# 03_-_28PINS_SCHEMATIC.net
KiCad netlist of a schematic drawn in Altium Designer
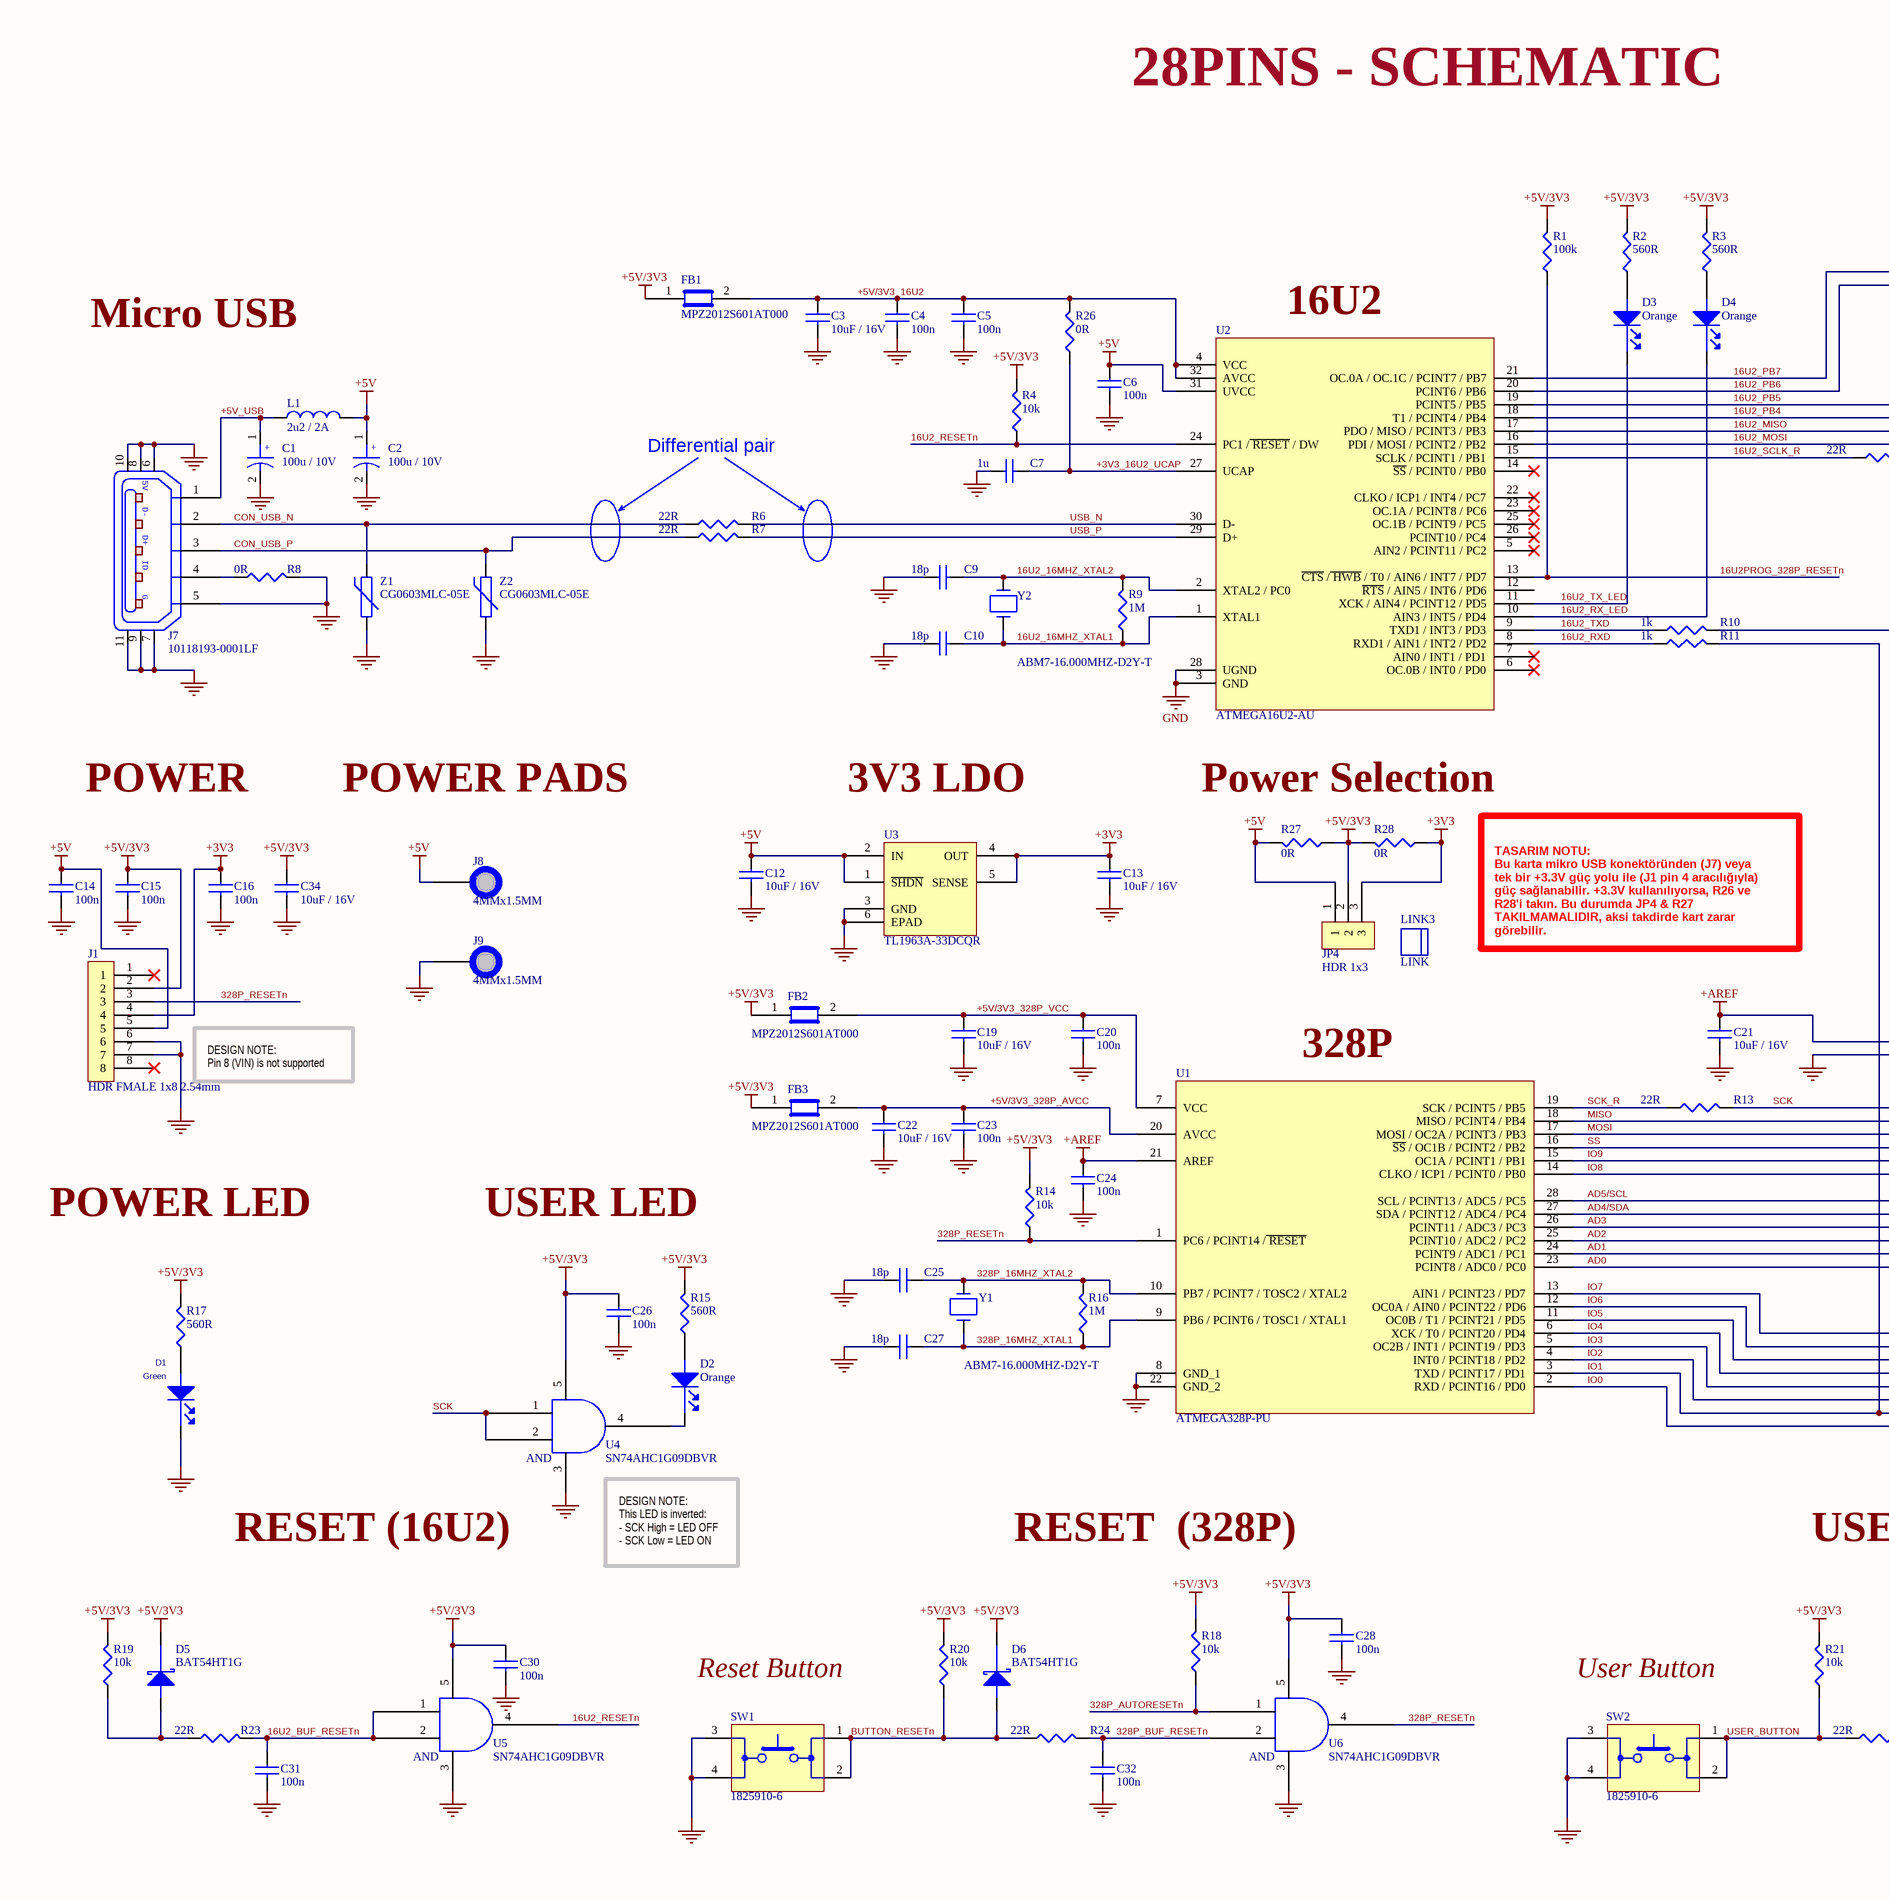
[diagram p0: [03] - 28PINS SCHEMATIC.SchDoc, left]
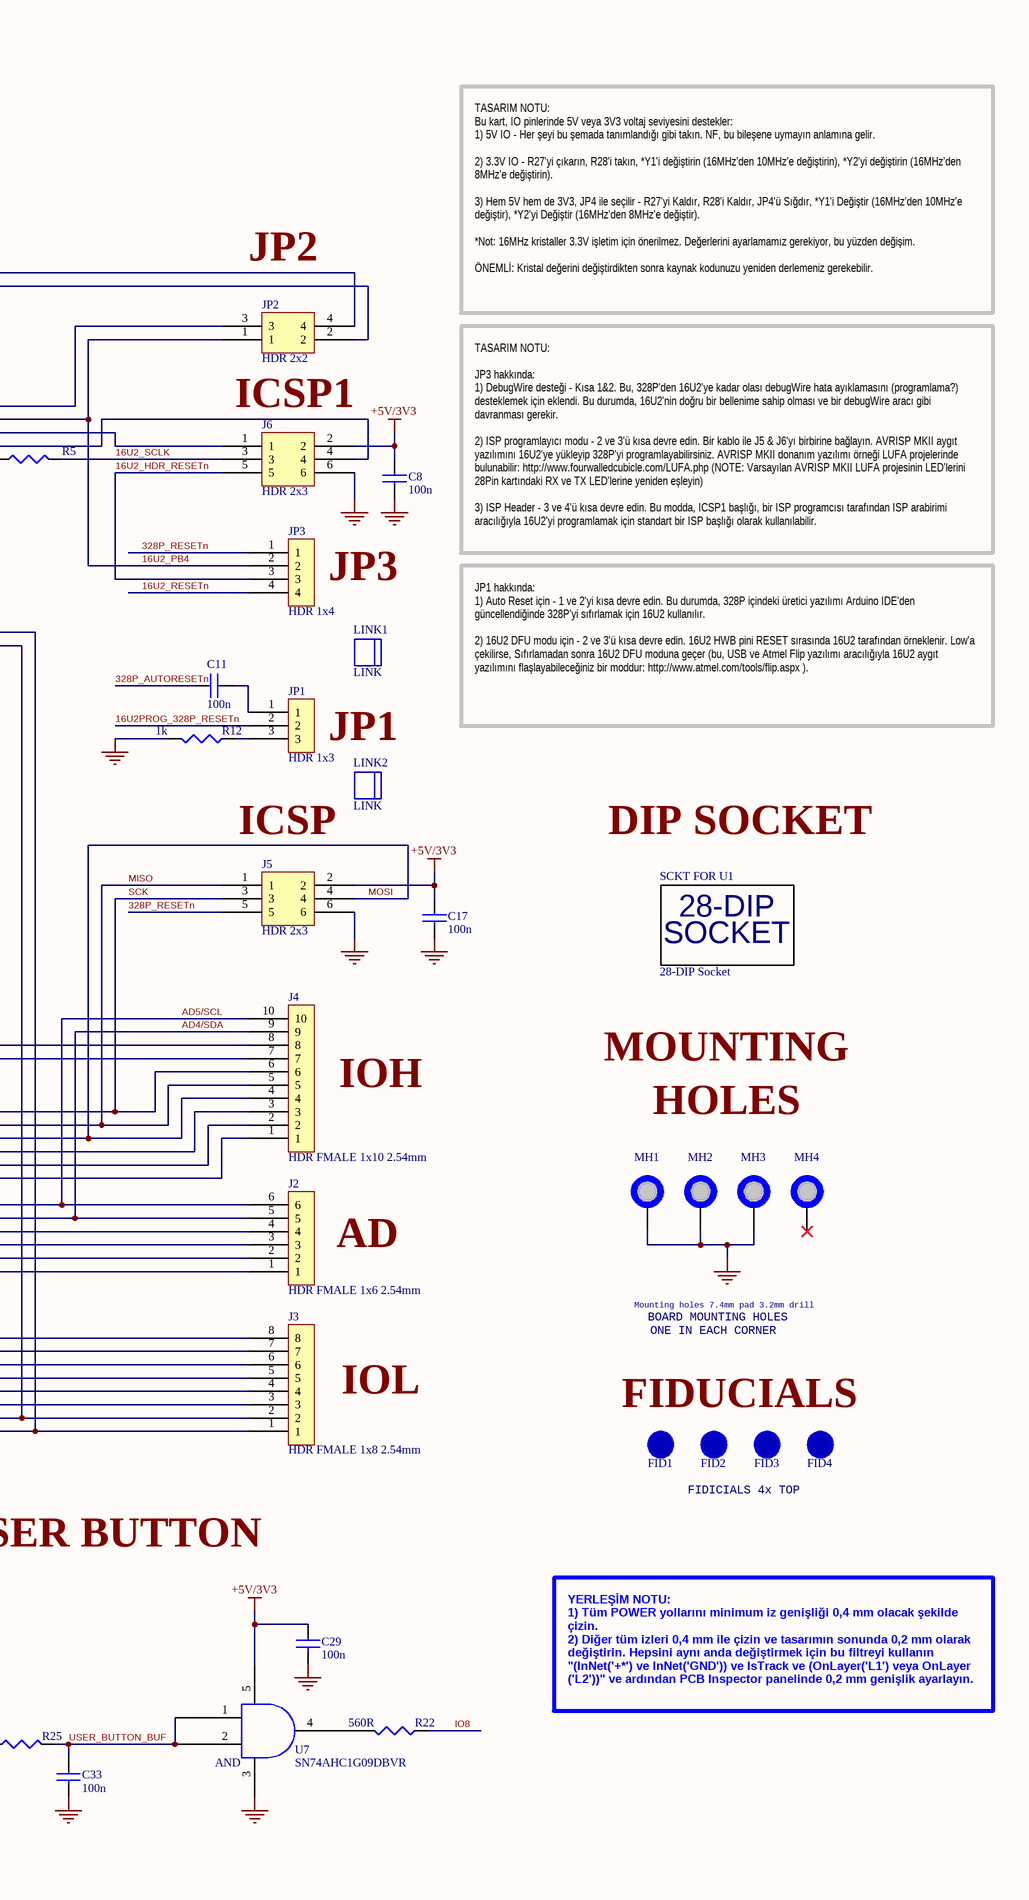
[diagram p1: [03] - 28PINS SCHEMATIC.SchDoc, right]

(export (version "E")
  (design (tool "Eeschema 10.0.6"))
  (components
    (comp (ref "C1")
      (value "100u / 10V")
      (footprint "C_ALU_C_SIZE")
      (description "CAP ALUM 100UF 10V 20% SMD")
      (fields
        (field (name "MANUFACTURER") "Panasonic Electronic Components")
        (field (name "MANUFACTURER PART NUMBER") "EEE-1AA101WR")
        (field (name ".CREATOR") "MM")
        (field (name ".CHECKED PCB") "RF")
        (field (name ".CHECKED SCH") "RF")
      )
      (libsource (lib "Integrated_Library_FEDEVEL_APR_2015") (part "EEE-1AA101WR"))
    )
    (comp (ref "C2")
      (value "100u / 10V")
      (footprint "C_ALU_C_SIZE")
      (description "CAP ALUM 100UF 10V 20% SMD")
      (fields
        (field (name "MANUFACTURER") "Panasonic Electronic Components")
        (field (name "MANUFACTURER PART NUMBER") "EEE-1AA101WR")
        (field (name ".CREATOR") "MM")
        (field (name ".CHECKED PCB") "RF")
        (field (name ".CHECKED SCH") "RF")
      )
      (libsource (lib "Integrated_Library_FEDEVEL_APR_2015") (part "EEE-1AA101WR"))
    )
    (comp (ref "C3")
      (value "10uF / 16V")
      (footprint "C0805")
      (description "CAP CER 10UF 16V 20% X5R 0805")
      (fields
        (field (name "MANUFACTURER") "TDK Corporation")
        (field (name "MANUFACTURER PART NUMBER") "C2012X5R1C106M/1.25")
      )
      (libsource (lib "Integrated_Library_FEDEVEL_APR_2015") (part "C2012X5R1C106M"))
    )
    (comp (ref "C4")
      (value "100n")
      (footprint "C0805")
      (description "CAP CER 0.1UF 50V 10% X7R 0805")
      (fields
        (field (name "MANUFACTURER") "TDK Corporation")
        (field (name "MANUFACTURER PART NUMBER") "C2012X7R1H104K085AA")
        (field (name ".CREATOR") "MM")
        (field (name ".CHECKED PCB") "RF")
        (field (name ".CHECKED SCH") "RF")
      )
      (libsource (lib "Integrated_Library_FEDEVEL_APR_2015") (part "C2012X7R1H104K085AA"))
    )
    (comp (ref "C5")
      (value "100n")
      (footprint "C0805")
      (description "CAP CER 0.1UF 50V 10% X7R 0805")
      (fields
        (field (name "MANUFACTURER") "TDK Corporation")
        (field (name "MANUFACTURER PART NUMBER") "C2012X7R1H104K085AA")
        (field (name ".CREATOR") "MM")
        (field (name ".CHECKED PCB") "RF")
        (field (name ".CHECKED SCH") "RF")
      )
      (libsource (lib "Integrated_Library_FEDEVEL_APR_2015") (part "C2012X7R1H104K085AA"))
    )
    (comp (ref "C6")
      (value "100n")
      (footprint "C0805")
      (description "CAP CER 0.1UF 50V 10% X7R 0805")
      (fields
        (field (name "MANUFACTURER") "TDK Corporation")
        (field (name "MANUFACTURER PART NUMBER") "C2012X7R1H104K085AA")
        (field (name ".CREATOR") "MM")
        (field (name ".CHECKED PCB") "RF")
        (field (name ".CHECKED SCH") "RF")
      )
      (libsource (lib "Integrated_Library_FEDEVEL_APR_2015") (part "C2012X7R1H104K085AA"))
    )
    (comp (ref "C7")
      (value "1u")
      (footprint "C0805")
      (description "CAP CER 1UF 25V 10% X5R 0805")
      (fields
        (field (name "MANUFACTURER") "TDK Corporation")
        (field (name "MANUFACTURER PART NUMBER") "C2012X5R1E105K125AA")
        (field (name ".CREATOR") "MM")
        (field (name ".CHECKED PCB") "RF")
        (field (name ".CHECKED SCH") "RF")
      )
      (libsource (lib "Integrated_Library_FEDEVEL_APR_2015") (part "C2012X5R1E105K125AA"))
    )
    (comp (ref "C8")
      (value "100n")
      (footprint "C0805")
      (description "CAP CER 0.1UF 50V 10% X7R 0805")
      (fields
        (field (name "MANUFACTURER") "TDK Corporation")
        (field (name "MANUFACTURER PART NUMBER") "C2012X7R1H104K085AA")
        (field (name ".CREATOR") "MM")
        (field (name ".CHECKED PCB") "RF")
        (field (name ".CHECKED SCH") "RF")
      )
      (libsource (lib "Integrated_Library_FEDEVEL_APR_2015") (part "C2012X7R1H104K085AA"))
    )
    (comp (ref "C9")
      (value "18p")
      (footprint "C0805")
      (description "CAP CER 18PF 50V 5% NP0 0805")
      (fields
        (field (name "MANUFACTURER") "Kemet")
        (field (name "MANUFACTURER PART NUMBER") "C0805C180J5GACTU")
        (field (name ".CREATOR") "MM")
        (field (name ".CHECKED PCB") "RF")
        (field (name ".CHECKED SCH") "RF")
      )
      (libsource (lib "Integrated_Library_FEDEVEL_APR_2015") (part "C0805C180J5GACTU"))
    )
    (comp (ref "C10")
      (value "18p")
      (footprint "C0805")
      (description "CAP CER 18PF 50V 5% NP0 0805")
      (fields
        (field (name "MANUFACTURER") "Kemet")
        (field (name "MANUFACTURER PART NUMBER") "C0805C180J5GACTU")
        (field (name ".CREATOR") "MM")
        (field (name ".CHECKED PCB") "RF")
        (field (name ".CHECKED SCH") "RF")
      )
      (libsource (lib "Integrated_Library_FEDEVEL_APR_2015") (part "C0805C180J5GACTU"))
    )
    (comp (ref "C11")
      (value "100n")
      (footprint "C0805")
      (description "CAP CER 0.1UF 50V 10% X7R 0805")
      (fields
        (field (name "MANUFACTURER") "TDK Corporation")
        (field (name "MANUFACTURER PART NUMBER") "C2012X7R1H104K085AA")
        (field (name ".CREATOR") "MM")
        (field (name ".CHECKED PCB") "RF")
        (field (name ".CHECKED SCH") "RF")
      )
      (libsource (lib "Integrated_Library_FEDEVEL_APR_2015") (part "C2012X7R1H104K085AA"))
    )
    (comp (ref "C12")
      (value "10uF / 16V")
      (footprint "C0805")
      (description "CAP CER 10UF 16V 20% X5R 0805")
      (fields
        (field (name "MANUFACTURER") "TDK Corporation")
        (field (name "MANUFACTURER PART NUMBER") "C2012X5R1C106M/1.25")
      )
      (libsource (lib "Integrated_Library_FEDEVEL_APR_2015") (part "C2012X5R1C106M"))
    )
    (comp (ref "C13")
      (value "10uF / 16V")
      (footprint "C0805")
      (description "CAP CER 10UF 16V 20% X5R 0805")
      (fields
        (field (name "MANUFACTURER") "TDK Corporation")
        (field (name "MANUFACTURER PART NUMBER") "C2012X5R1C106M/1.25")
      )
      (libsource (lib "Integrated_Library_FEDEVEL_APR_2015") (part "C2012X5R1C106M"))
    )
    (comp (ref "C14")
      (value "100n")
      (footprint "C0805")
      (description "CAP CER 0.1UF 50V 10% X7R 0805")
      (fields
        (field (name "MANUFACTURER") "TDK Corporation")
        (field (name "MANUFACTURER PART NUMBER") "C2012X7R1H104K085AA")
        (field (name ".CREATOR") "MM")
        (field (name ".CHECKED PCB") "RF")
        (field (name ".CHECKED SCH") "RF")
      )
      (libsource (lib "Integrated_Library_FEDEVEL_APR_2015") (part "C2012X7R1H104K085AA"))
    )
    (comp (ref "C15")
      (value "100n")
      (footprint "C0805")
      (description "CAP CER 0.1UF 50V 10% X7R 0805")
      (fields
        (field (name "MANUFACTURER") "TDK Corporation")
        (field (name "MANUFACTURER PART NUMBER") "C2012X7R1H104K085AA")
        (field (name ".CREATOR") "MM")
        (field (name ".CHECKED PCB") "RF")
        (field (name ".CHECKED SCH") "RF")
      )
      (libsource (lib "Integrated_Library_FEDEVEL_APR_2015") (part "C2012X7R1H104K085AA"))
    )
    (comp (ref "C16")
      (value "100n")
      (footprint "C0805")
      (description "CAP CER 0.1UF 50V 10% X7R 0805")
      (fields
        (field (name "MANUFACTURER") "TDK Corporation")
        (field (name "MANUFACTURER PART NUMBER") "C2012X7R1H104K085AA")
        (field (name ".CREATOR") "MM")
        (field (name ".CHECKED PCB") "RF")
        (field (name ".CHECKED SCH") "RF")
      )
      (libsource (lib "Integrated_Library_FEDEVEL_APR_2015") (part "C2012X7R1H104K085AA"))
    )
    (comp (ref "C17")
      (value "100n")
      (footprint "C0805")
      (description "CAP CER 0.1UF 50V 10% X7R 0805")
      (fields
        (field (name "MANUFACTURER") "TDK Corporation")
        (field (name "MANUFACTURER PART NUMBER") "C2012X7R1H104K085AA")
        (field (name ".CREATOR") "MM")
        (field (name ".CHECKED PCB") "RF")
        (field (name ".CHECKED SCH") "RF")
      )
      (libsource (lib "Integrated_Library_FEDEVEL_APR_2015") (part "C2012X7R1H104K085AA"))
    )
    (comp (ref "C19")
      (value "10uF / 16V")
      (footprint "C0805")
      (description "CAP CER 10UF 16V 20% X5R 0805")
      (fields
        (field (name "MANUFACTURER") "TDK Corporation")
        (field (name "MANUFACTURER PART NUMBER") "C2012X5R1C106M/1.25")
      )
      (libsource (lib "Integrated_Library_FEDEVEL_APR_2015") (part "C2012X5R1C106M"))
    )
    (comp (ref "C20")
      (value "100n")
      (footprint "C0805")
      (description "CAP CER 0.1UF 50V 10% X7R 0805")
      (fields
        (field (name "MANUFACTURER") "TDK Corporation")
        (field (name "MANUFACTURER PART NUMBER") "C2012X7R1H104K085AA")
        (field (name ".CREATOR") "MM")
        (field (name ".CHECKED PCB") "RF")
        (field (name ".CHECKED SCH") "RF")
      )
      (libsource (lib "Integrated_Library_FEDEVEL_APR_2015") (part "C2012X7R1H104K085AA"))
    )
    (comp (ref "C21")
      (value "10uF / 16V")
      (footprint "C0805")
      (description "CAP CER 10UF 16V 20% X5R 0805")
      (fields
        (field (name "MANUFACTURER") "TDK Corporation")
        (field (name "MANUFACTURER PART NUMBER") "C2012X5R1C106M/1.25")
      )
      (libsource (lib "Integrated_Library_FEDEVEL_APR_2015") (part "C2012X5R1C106M"))
    )
    (comp (ref "C22")
      (value "10uF / 16V")
      (footprint "C0805")
      (description "CAP CER 10UF 16V 20% X5R 0805")
      (fields
        (field (name "MANUFACTURER") "TDK Corporation")
        (field (name "MANUFACTURER PART NUMBER") "C2012X5R1C106M/1.25")
      )
      (libsource (lib "Integrated_Library_FEDEVEL_APR_2015") (part "C2012X5R1C106M"))
    )
    (comp (ref "C23")
      (value "100n")
      (footprint "C0805")
      (description "CAP CER 0.1UF 50V 10% X7R 0805")
      (fields
        (field (name "MANUFACTURER") "TDK Corporation")
        (field (name "MANUFACTURER PART NUMBER") "C2012X7R1H104K085AA")
        (field (name ".CREATOR") "MM")
        (field (name ".CHECKED PCB") "RF")
        (field (name ".CHECKED SCH") "RF")
      )
      (libsource (lib "Integrated_Library_FEDEVEL_APR_2015") (part "C2012X7R1H104K085AA"))
    )
    (comp (ref "C24")
      (value "100n")
      (footprint "C0805")
      (description "CAP CER 0.1UF 50V 10% X7R 0805")
      (fields
        (field (name "MANUFACTURER") "TDK Corporation")
        (field (name "MANUFACTURER PART NUMBER") "C2012X7R1H104K085AA")
        (field (name ".CREATOR") "MM")
        (field (name ".CHECKED PCB") "RF")
        (field (name ".CHECKED SCH") "RF")
      )
      (libsource (lib "Integrated_Library_FEDEVEL_APR_2015") (part "C2012X7R1H104K085AA"))
    )
    (comp (ref "C25")
      (value "18p")
      (footprint "C0805")
      (description "CAP CER 18PF 50V 5% NP0 0805")
      (fields
        (field (name "MANUFACTURER") "Kemet")
        (field (name "MANUFACTURER PART NUMBER") "C0805C180J5GACTU")
        (field (name ".CREATOR") "MM")
        (field (name ".CHECKED PCB") "RF")
        (field (name ".CHECKED SCH") "RF")
      )
      (libsource (lib "Integrated_Library_FEDEVEL_APR_2015") (part "C0805C180J5GACTU"))
    )
    (comp (ref "C26")
      (value "100n")
      (footprint "C0805")
      (description "CAP CER 0.1UF 50V 10% X7R 0805")
      (fields
        (field (name "MANUFACTURER") "TDK Corporation")
        (field (name "MANUFACTURER PART NUMBER") "C2012X7R1H104K085AA")
        (field (name ".CREATOR") "MM")
        (field (name ".CHECKED PCB") "RF")
        (field (name ".CHECKED SCH") "RF")
      )
      (libsource (lib "Integrated_Library_FEDEVEL_APR_2015") (part "C2012X7R1H104K085AA"))
    )
    (comp (ref "C27")
      (value "18p")
      (footprint "C0805")
      (description "CAP CER 18PF 50V 5% NP0 0805")
      (fields
        (field (name "MANUFACTURER") "Kemet")
        (field (name "MANUFACTURER PART NUMBER") "C0805C180J5GACTU")
        (field (name ".CREATOR") "MM")
        (field (name ".CHECKED PCB") "RF")
        (field (name ".CHECKED SCH") "RF")
      )
      (libsource (lib "Integrated_Library_FEDEVEL_APR_2015") (part "C0805C180J5GACTU"))
    )
    (comp (ref "C28")
      (value "100n")
      (footprint "C0805")
      (description "CAP CER 0.1UF 50V 10% X7R 0805")
      (fields
        (field (name "MANUFACTURER") "TDK Corporation")
        (field (name "MANUFACTURER PART NUMBER") "C2012X7R1H104K085AA")
        (field (name ".CREATOR") "MM")
        (field (name ".CHECKED PCB") "RF")
        (field (name ".CHECKED SCH") "RF")
      )
      (libsource (lib "Integrated_Library_FEDEVEL_APR_2015") (part "C2012X7R1H104K085AA"))
    )
    (comp (ref "C29")
      (value "100n")
      (footprint "C0805")
      (description "CAP CER 0.1UF 50V 10% X7R 0805")
      (fields
        (field (name "MANUFACTURER") "TDK Corporation")
        (field (name "MANUFACTURER PART NUMBER") "C2012X7R1H104K085AA")
        (field (name ".CREATOR") "MM")
        (field (name ".CHECKED PCB") "RF")
        (field (name ".CHECKED SCH") "RF")
      )
      (libsource (lib "Integrated_Library_FEDEVEL_APR_2015") (part "C2012X7R1H104K085AA"))
    )
    (comp (ref "C30")
      (value "100n")
      (footprint "C0805")
      (description "CAP CER 0.1UF 50V 10% X7R 0805")
      (fields
        (field (name "MANUFACTURER") "TDK Corporation")
        (field (name "MANUFACTURER PART NUMBER") "C2012X7R1H104K085AA")
        (field (name ".CREATOR") "MM")
        (field (name ".CHECKED PCB") "RF")
        (field (name ".CHECKED SCH") "RF")
      )
      (libsource (lib "Integrated_Library_FEDEVEL_APR_2015") (part "C2012X7R1H104K085AA"))
    )
    (comp (ref "C31")
      (value "100n")
      (footprint "C0805")
      (description "CAP CER 0.1UF 50V 10% X7R 0805")
      (fields
        (field (name "MANUFACTURER") "TDK Corporation")
        (field (name "MANUFACTURER PART NUMBER") "C2012X7R1H104K085AA")
        (field (name ".CREATOR") "MM")
        (field (name ".CHECKED PCB") "RF")
        (field (name ".CHECKED SCH") "RF")
      )
      (libsource (lib "Integrated_Library_FEDEVEL_APR_2015") (part "C2012X7R1H104K085AA"))
    )
    (comp (ref "C32")
      (value "100n")
      (footprint "C0805")
      (description "CAP CER 0.1UF 50V 10% X7R 0805")
      (fields
        (field (name "MANUFACTURER") "TDK Corporation")
        (field (name "MANUFACTURER PART NUMBER") "C2012X7R1H104K085AA")
        (field (name ".CREATOR") "MM")
        (field (name ".CHECKED PCB") "RF")
        (field (name ".CHECKED SCH") "RF")
      )
      (libsource (lib "Integrated_Library_FEDEVEL_APR_2015") (part "C2012X7R1H104K085AA"))
    )
    (comp (ref "C33")
      (value "100n")
      (footprint "C0805")
      (description "CAP CER 0.1UF 50V 10% X7R 0805")
      (fields
        (field (name "MANUFACTURER") "TDK Corporation")
        (field (name "MANUFACTURER PART NUMBER") "C2012X7R1H104K085AA")
        (field (name ".CREATOR") "MM")
        (field (name ".CHECKED PCB") "RF")
        (field (name ".CHECKED SCH") "RF")
      )
      (libsource (lib "Integrated_Library_FEDEVEL_APR_2015") (part "C2012X7R1H104K085AA"))
    )
    (comp (ref "C34")
      (value "10uF / 16V")
      (footprint "C0805")
      (description "CAP CER 10UF 16V 20% X5R 0805")
      (fields
        (field (name "MANUFACTURER") "TDK Corporation")
        (field (name "MANUFACTURER PART NUMBER") "C2012X5R1C106M/1.25")
      )
      (libsource (lib "Integrated_Library_FEDEVEL_APR_2015") (part "C2012X5R1C106M"))
    )
    (comp (ref "D1")
      (value "Green")
      (footprint "LED_0603")
      (description "LED SMARTLED GREEN 570NM 0603")
      (fields
        (field (name "MANUFACTURER") "OSRAM Opto Semiconductors Inc")
        (field (name "MANUFACTURER PART NUMBER") "LG L29K-G2J1-24-Z")
      )
      (libsource (lib "Integrated_Library_FEDEVEL_APR_2015") (part "LG L29K-G2J1-24-Z"))
    )
    (comp (ref "D2")
      (value "Orange")
      (footprint "LED_0603")
      (description "LED SMARTLED ORANGE 606NM 0603")
      (fields
        (field (name "MANUFACTURER") "OSRAM Opto Semiconductors Inc")
        (field (name "MANUFACTURER PART NUMBER") "LO L29K-H2K1-24-Z")
      )
      (libsource (lib "Integrated_Library_FEDEVEL_APR_2015") (part "LO L29K-H2K1-24-Z"))
    )
    (comp (ref "D3")
      (value "Orange")
      (footprint "LED_0603")
      (description "LED SMARTLED ORANGE 606NM 0603")
      (fields
        (field (name "MANUFACTURER") "OSRAM Opto Semiconductors Inc")
        (field (name "MANUFACTURER PART NUMBER") "LO L29K-H2K1-24-Z")
      )
      (libsource (lib "Integrated_Library_FEDEVEL_APR_2015") (part "LO L29K-H2K1-24-Z"))
    )
    (comp (ref "D4")
      (value "Orange")
      (footprint "LED_0603")
      (description "LED SMARTLED ORANGE 606NM 0603")
      (fields
        (field (name "MANUFACTURER") "OSRAM Opto Semiconductors Inc")
        (field (name "MANUFACTURER PART NUMBER") "LO L29K-H2K1-24-Z")
      )
      (libsource (lib "Integrated_Library_FEDEVEL_APR_2015") (part "LO L29K-H2K1-24-Z"))
    )
    (comp (ref "D5")
      (value "BAT54HT1G")
      (footprint "SOD323")
      (description "DIODE SCHOTTKY 30V 0.2A SOD323")
      (fields (field (name "MANUFACTURER") "Fairchild Semiconductor") (field (name ".CREATOR") "MM"))
      (libsource (lib "Integrated_Library_FEDEVEL_APR_2015") (part "BAT54HT1G"))
    )
    (comp (ref "D6")
      (value "BAT54HT1G")
      (footprint "SOD323")
      (description "DIODE SCHOTTKY 30V 0.2A SOD323")
      (fields (field (name "MANUFACTURER") "Fairchild Semiconductor") (field (name ".CREATOR") "MM"))
      (libsource (lib "Integrated_Library_FEDEVEL_APR_2015") (part "BAT54HT1G"))
    )
    (comp (ref "FB1")
      (value "MPZ2012S601AT000")
      (footprint "C0805")
      (description "FERRITE CHIP BEAD 600 OHM SMD")
      (fields
        (field (name "MANUFACTURER") "TDK Corporation")
        (field (name ".CREATOR") "MM")
        (field (name ".CHECKED PCB") "RF")
        (field (name ".CHECKED SCH") "RF")
      )
      (libsource (lib "Integrated_Library_FEDEVEL_APR_2015") (part "MPZ2012S601AT000"))
    )
    (comp (ref "FB2")
      (value "MPZ2012S601AT000")
      (footprint "C0805")
      (description "FERRITE CHIP BEAD 600 OHM SMD")
      (fields
        (field (name "MANUFACTURER") "TDK Corporation")
        (field (name ".CREATOR") "MM")
        (field (name ".CHECKED PCB") "RF")
        (field (name ".CHECKED SCH") "RF")
      )
      (libsource (lib "Integrated_Library_FEDEVEL_APR_2015") (part "MPZ2012S601AT000"))
    )
    (comp (ref "FB3")
      (value "MPZ2012S601AT000")
      (footprint "C0805")
      (description "FERRITE CHIP BEAD 600 OHM SMD")
      (fields
        (field (name "MANUFACTURER") "TDK Corporation")
        (field (name ".CREATOR") "MM")
        (field (name ".CHECKED PCB") "RF")
        (field (name ".CHECKED SCH") "RF")
      )
      (libsource (lib "Integrated_Library_FEDEVEL_APR_2015") (part "MPZ2012S601AT000"))
    )
    (comp (ref "FID1")
      (value "FID_1MMC")
      (footprint "FID_40X120D")
      (description "Fiducial 40mil Diameter, 120mil Mask")
      (libsource (lib "Integrated_Library_FEDEVEL_APR_2015") (part "FID_1MMC"))
    )
    (comp (ref "FID2")
      (value "FID_1MMC")
      (footprint "FID_40X120D")
      (description "Fiducial 40mil Diameter, 120mil Mask")
      (libsource (lib "Integrated_Library_FEDEVEL_APR_2015") (part "FID_1MMC"))
    )
    (comp (ref "FID3")
      (value "FID_1MMC")
      (footprint "FID_40X120D")
      (description "Fiducial 40mil Diameter, 120mil Mask")
      (libsource (lib "Integrated_Library_FEDEVEL_APR_2015") (part "FID_1MMC"))
    )
    (comp (ref "FID4")
      (value "FID_1MMC")
      (footprint "FID_40X120D")
      (description "Fiducial 40mil Diameter, 120mil Mask")
      (libsource (lib "Integrated_Library_FEDEVEL_APR_2015") (part "FID_1MMC"))
    )
    (comp (ref "J1")
      (value "HDR FMALE 1x8 2.54mm")
      (footprint "Hdr_Female_1x8_2.54mm")
      (description "08-WAY SIL VERT SOCKET L/FREE")
      (fields
        (field (name "MANUFACTURER") "Harwin Inc")
        (field (name "MANUFACTURER PART NUMBER") "M20-7820842")
        (field (name ".CREATOR") "MM")
        (field (name ".CHECKED PCB") "RF")
        (field (name ".CHECKED SCH") "RF")
      )
      (libsource (lib "Integrated_Library_FEDEVEL_APR_2015") (part "M20-7820842"))
    )
    (comp (ref "J2")
      (value "HDR FMALE 1x6 2.54mm")
      (footprint "Hdr_Female_1x6_2.54mm")
      (description "06-WAY SIL VERT SOCKET L/FREE")
      (fields
        (field (name "MANUFACTURER") "Harwin Inc")
        (field (name "MANUFACTURER PART NUMBER") "M20-7820646")
        (field (name ".CHECKED PCB") "MM")
        (field (name ".CHECKED SCH") "MM")
        (field (name ".CREATOR") "MM")
      )
      (libsource (lib "Integrated_Library_FEDEVEL_APR_2015") (part "M20-7820646"))
    )
    (comp (ref "J3")
      (value "HDR FMALE 1x8 2.54mm")
      (footprint "Hdr_Female_1x8_2.54mm")
      (description "08-WAY SIL VERT SOCKET L/FREE")
      (fields
        (field (name "MANUFACTURER") "Harwin Inc")
        (field (name "MANUFACTURER PART NUMBER") "M20-7820842")
        (field (name ".CREATOR") "MM")
        (field (name ".CHECKED PCB") "RF")
        (field (name ".CHECKED SCH") "RF")
      )
      (libsource (lib "") (part "M20-7820842_1"))
    )
    (comp (ref "J4")
      (value "HDR FMALE 1x10 2.54mm")
      (footprint "Hdr_Female_1x10_2.54mm")
      (description "10-WAY SIL VERT SOCKET L/FREE")
      (fields
        (field (name "MANUFACTURER") "Harwin Inc")
        (field (name "MANUFACTURER PART NUMBER") "M20-7821046")
        (field (name ".CREATOR") "MM")
        (field (name ".CHECKED PCB") "RF")
        (field (name ".CHECKED SCH") "RF")
      )
      (libsource (lib "Integrated_Library_FEDEVEL_APR_2015") (part "M20-7821046"))
    )
    (comp (ref "J5")
      (value "HDR 2x3")
      (footprint "HDR_2x3_2.54MM")
      (description "CONN HEADER 6POS .100 STR 30AU")
      (fields
        (field (name "MANUFACTURER") "FCI")
        (field (name "MANUFACTURER PART NUMBER") "67997-106HLF")
        (field (name ".CREATOR") "MM")
        (field (name ".CHECKED PCB") "RF")
        (field (name ".CHECKED SCH") "RF")
      )
      (libsource (lib "Integrated_Library_FEDEVEL_APR_2015") (part "67997-106HLF"))
    )
    (comp (ref "J6")
      (value "HDR 2x3")
      (footprint "HDR_2x3_2.54MM")
      (description "CONN HEADER 6POS .100 STR 30AU")
      (fields
        (field (name "MANUFACTURER") "FCI")
        (field (name "MANUFACTURER PART NUMBER") "67997-106HLF")
        (field (name ".CREATOR") "MM")
        (field (name ".CHECKED PCB") "RF")
        (field (name ".CHECKED SCH") "RF")
      )
      (libsource (lib "Integrated_Library_FEDEVEL_APR_2015") (part "67997-106HLF"))
    )
    (comp (ref "J7")
      (value "10118193-0001LF")
      (footprint "10118193")
      (description "CONN USB MICRO B RECPT SMT R/A")
      (fields
        (field (name "MANUFACTURER") "FCI")
        (field (name ".CREATOR") "MM")
        (field (name ".CHECKED PCB") "RF")
        (field (name ".CHECKED SCH") "MM")
      )
      (libsource (lib "Integrated_Library_FEDEVEL_APR_2015") (part "10118193-0001LF"))
    )
    (comp (ref "J8")
      (value "4MMx1.5MM")
      (footprint "PAD_WITH_HOLE_4MMx1.5MM")
      (description "Pad with a hole 4mm x 1.5mm")
      (libsource (lib "Integrated_Library_FEDEVEL_APR_2015") (part "PAD_WITH_HOLE_4MMx1.5MM"))
    )
    (comp (ref "J9")
      (value "4MMx1.5MM")
      (footprint "PAD_WITH_HOLE_4MMx1.5MM")
      (description "Pad with a hole 4mm x 1.5mm")
      (libsource (lib "Integrated_Library_FEDEVEL_APR_2015") (part "PAD_WITH_HOLE_4MMx1.5MM"))
    )
    (comp (ref "JP1")
      (value "HDR 1x3")
      (footprint "Hdr_1x3_2.54mm")
      (description "BERGSTIK II .100\" SR STRAIGHT")
      (fields
        (field (name "MANUFACTURER") "FCI")
        (field (name "MANUFACTURER PART NUMBER") "68000-103HLF")
        (field (name ".CREATOR") "MM")
      )
      (libsource (lib "Integrated_Library_FEDEVEL_APR_2015") (part "68000-103HLF"))
    )
    (comp (ref "JP2")
      (value "HDR 2x2")
      (footprint "HDR_2x2_2.54MM")
      (description "CONN HEADER 4POS .100 STR 15AU")
      (fields
        (field (name "MANUFACTURER") "FCI")
        (field (name "MANUFACTURER PART NUMBER") "68602-204HLF")
        (field (name ".CREATOR") "MM")
        (field (name ".CHECKED PCB") "RF")
        (field (name ".CHECKED SCH") "RF")
      )
      (libsource (lib "Integrated_Library_FEDEVEL_APR_2015") (part "68602-204HLF"))
    )
    (comp (ref "JP3")
      (value "HDR 1x4")
      (footprint "HDR_1x4_2.54MM")
      (description "CONN HEADER 4POS .100 STR 15AU")
      (fields
        (field (name "MANUFACTURER") "FCI")
        (field (name "MANUFACTURER PART NUMBER") "68001-204HLF")
        (field (name ".CHECKED PCB") "RF")
        (field (name ".CHECKED SCH") "RF")
      )
      (libsource (lib "Integrated_Library_FEDEVEL_APR_2015") (part "68001-204HLF"))
    )
    (comp (ref "JP4")
      (value "HDR 1x3")
      (footprint "Hdr_1x3_2.54mm")
      (description "BERGSTIK II .100\" SR STRAIGHT")
      (fields
        (field (name "MANUFACTURER") "FCI")
        (field (name "MANUFACTURER PART NUMBER") "68000-103HLF")
        (field (name ".CREATOR") "MM")
      )
      (libsource (lib "") (part "68000-103HLF_1"))
    )
    (comp (ref "L1")
      (value "2u2 / 2A")
      (footprint "C1210_IND")
      (description "FIXED IND 2.2UH 2A 80 MOHM SMD")
      (fields
        (field (name "MANUFACTURER") "Kemet")
        (field (name "MANUFACTURER PART NUMBER") "L1210R2R2MDWIT")
        (field (name ".CREATOR") "MM")
        (field (name ".CHECKED PCB") "RF")
        (field (name ".CHECKED SCH") "RF")
      )
      (libsource (lib "Integrated_Library_FEDEVEL_APR_2015") (part "L1210R2R2MDWIT"))
    )
    (comp (ref "LINK1")
      (value "LINK")
      (description "CONN JUMPER SHORTING .100\" GOLD")
      (fields
        (field (name "MANUFACTURER") "Sullins Connector Solutions")
        (field (name "MANUFACTURER PART NUMBER") "QPC02SXGN-RC")
      )
      (libsource (lib "Integrated_Library_FEDEVEL_APR_2015") (part "QPC02SXGN-RC"))
    )
    (comp (ref "LINK2")
      (value "LINK")
      (description "CONN JUMPER SHORTING .100\" GOLD")
      (fields
        (field (name "MANUFACTURER") "Sullins Connector Solutions")
        (field (name "MANUFACTURER PART NUMBER") "QPC02SXGN-RC")
      )
      (libsource (lib "Integrated_Library_FEDEVEL_APR_2015") (part "QPC02SXGN-RC"))
    )
    (comp (ref "LINK3")
      (value "LINK")
      (description "CONN JUMPER SHORTING .100\" GOLD")
      (fields
        (field (name "MANUFACTURER") "Sullins Connector Solutions")
        (field (name "MANUFACTURER PART NUMBER") "QPC02SXGN-RC")
      )
      (libsource (lib "Integrated_Library_FEDEVEL_APR_2015") (part "QPC02SXGN-RC"))
    )
    (comp (ref "MH1")
      (value "MH_7.4MMC_3.2MMD")
      (footprint "MH_7.4MMD_3.2MMD")
      (description "Mounting Hole 7.4mm Diameter, 3.2mm Drill")
      (fields (field (name ".CREATOR") "MM"))
      (libsource (lib "Integrated_Library_FEDEVEL_APR_2015") (part "MH_7.4MMC_3.2MMD"))
    )
    (comp (ref "MH2")
      (value "MH_7.4MMC_3.2MMD")
      (footprint "MH_7.4MMD_3.2MMD")
      (description "Mounting Hole 7.4mm Diameter, 3.2mm Drill")
      (fields (field (name ".CREATOR") "MM"))
      (libsource (lib "Integrated_Library_FEDEVEL_APR_2015") (part "MH_7.4MMC_3.2MMD"))
    )
    (comp (ref "MH3")
      (value "MH_7.4MMC_3.2MMD")
      (footprint "MH_7.4MMD_3.2MMD")
      (description "Mounting Hole 7.4mm Diameter, 3.2mm Drill")
      (fields (field (name ".CREATOR") "MM"))
      (libsource (lib "Integrated_Library_FEDEVEL_APR_2015") (part "MH_7.4MMC_3.2MMD"))
    )
    (comp (ref "MH4")
      (value "MH_7.4MMNC_3.2MMD")
      (footprint "MH_7.4MMD_3.2MMD_NON_COPPER_NPTH")
      (description "Mounting Hole 7.4mm Diameter (Non Copper), 3.2mm Drill NPTH")
      (libsource (lib "Integrated_Library_FEDEVEL_APR_2015") (part "MH_7.4MMNC_3.2MMD"))
    )
    (comp (ref "R1")
      (value "100k")
      (footprint "R0805")
      (description "RES SMD 100K OHM 1% 1/8W 0805")
      (fields
        (field (name "MANUFACTURER") "Yageo")
        (field (name "MANUFACTURER PART NUMBER") "RC0805FR-07100KL")
        (field (name ".CREATOR") "MM")
        (field (name ".CHECKED PCB") "RF")
        (field (name ".CHECKED SCH") "RF")
      )
      (libsource (lib "Integrated_Library_FEDEVEL_APR_2015") (part "RC0805FR-07100KL"))
    )
    (comp (ref "R2")
      (value "560R")
      (footprint "R0805")
      (description "RES SMD 560 OHM 1% 1/8W 0805")
      (fields
        (field (name "MANUFACTURER") "Yageo")
        (field (name "MANUFACTURER PART NUMBER") "RC0805FR-07560RL")
        (field (name ".CREATOR") "MM")
        (field (name ".CHECKED PCB") "RF")
        (field (name ".CHECKED SCH") "RF")
      )
      (libsource (lib "Integrated_Library_FEDEVEL_APR_2015") (part "RC0805FR-07560RL"))
    )
    (comp (ref "R3")
      (value "560R")
      (footprint "R0805")
      (description "RES SMD 560 OHM 1% 1/8W 0805")
      (fields
        (field (name "MANUFACTURER") "Yageo")
        (field (name "MANUFACTURER PART NUMBER") "RC0805FR-07560RL")
        (field (name ".CREATOR") "MM")
        (field (name ".CHECKED PCB") "RF")
        (field (name ".CHECKED SCH") "RF")
      )
      (libsource (lib "Integrated_Library_FEDEVEL_APR_2015") (part "RC0805FR-07560RL"))
    )
    (comp (ref "R4")
      (value "10k")
      (footprint "R0805")
      (description "RES SMD 10K OHM 1% 1/8W 0805")
      (fields
        (field (name "MANUFACTURER") "Yageo")
        (field (name "MANUFACTURER PART NUMBER") "RC0805FR-0710KL")
        (field (name ".CREATOR") "MM")
        (field (name ".CHECKED PCB") "RF")
        (field (name ".CHECKED SCH") "RF")
      )
      (libsource (lib "Integrated_Library_FEDEVEL_APR_2015") (part "RC0805FR-0710KL"))
    )
    (comp (ref "R5")
      (value "22R")
      (footprint "R0805")
      (description "RES SMD 22 OHM 1% 1/8W 0805")
      (fields
        (field (name "MANUFACTURER") "Yageo")
        (field (name "MANUFACTURER PART NUMBER") "RC0805FR-0722RL")
        (field (name ".CREATOR") "MM")
        (field (name ".CHECKED PCB") "RF")
        (field (name ".CHECKED SCH") "RF")
      )
      (libsource (lib "Integrated_Library_FEDEVEL_APR_2015") (part "RC0805FR-0722RL"))
    )
    (comp (ref "R6")
      (value "22R")
      (footprint "R0805")
      (description "RES SMD 22 OHM 1% 1/8W 0805")
      (fields
        (field (name "MANUFACTURER") "Yageo")
        (field (name "MANUFACTURER PART NUMBER") "RC0805FR-0722RL")
        (field (name ".CREATOR") "MM")
        (field (name ".CHECKED PCB") "RF")
        (field (name ".CHECKED SCH") "RF")
      )
      (libsource (lib "Integrated_Library_FEDEVEL_APR_2015") (part "RC0805FR-0722RL"))
    )
    (comp (ref "R7")
      (value "22R")
      (footprint "R0805")
      (description "RES SMD 22 OHM 1% 1/8W 0805")
      (fields
        (field (name "MANUFACTURER") "Yageo")
        (field (name "MANUFACTURER PART NUMBER") "RC0805FR-0722RL")
        (field (name ".CREATOR") "MM")
        (field (name ".CHECKED PCB") "RF")
        (field (name ".CHECKED SCH") "RF")
      )
      (libsource (lib "Integrated_Library_FEDEVEL_APR_2015") (part "RC0805FR-0722RL"))
    )
    (comp (ref "R8")
      (value "0R")
      (footprint "R0805")
      (description "RES 0.0 OHM 1/8W 0805 SMD")
      (fields
        (field (name "MANUFACTURER") "Yageo")
        (field (name "MANUFACTURER PART NUMBER") "RC0805JR-070RL")
        (field (name ".CHECKED PCB") "RF")
        (field (name ".CHECKED SCH") "RF")
      )
      (libsource (lib "Integrated_Library_FEDEVEL_APR_2015") (part "RC0805JR-070RL"))
    )
    (comp (ref "R9")
      (value "1M")
      (footprint "R0805")
      (description "RES SMD 1M OHM 1% 1/8W 0805")
      (fields
        (field (name "MANUFACTURER") "Yageo")
        (field (name "MANUFACTURER PART NUMBER") "RC0805FR-071ML")
        (field (name ".CREATOR") "MM")
        (field (name ".CHECKED PCB") "RF")
        (field (name ".CHECKED SCH") "RF")
      )
      (libsource (lib "Integrated_Library_FEDEVEL_APR_2015") (part "RC0805FR-071ML"))
    )
    (comp (ref "R10")
      (value "1k")
      (footprint "R0805")
      (description "RES SMD 1K OHM 1% 1/8W 0805")
      (fields
        (field (name "MANUFACTURER") "Yageo")
        (field (name "MANUFACTURER PART NUMBER") "RC0805FR-071KL")
        (field (name ".CREATOR") "MM")
        (field (name ".CHECKED PCB") "RF")
        (field (name ".CHECKED SCH") "RF")
      )
      (libsource (lib "Integrated_Library_FEDEVEL_APR_2015") (part "RC0805FR-071KL"))
    )
    (comp (ref "R11")
      (value "1k")
      (footprint "R0805")
      (description "RES SMD 1K OHM 1% 1/8W 0805")
      (fields
        (field (name "MANUFACTURER") "Yageo")
        (field (name "MANUFACTURER PART NUMBER") "RC0805FR-071KL")
        (field (name ".CREATOR") "MM")
        (field (name ".CHECKED PCB") "RF")
        (field (name ".CHECKED SCH") "RF")
      )
      (libsource (lib "Integrated_Library_FEDEVEL_APR_2015") (part "RC0805FR-071KL"))
    )
    (comp (ref "R12")
      (value "1k")
      (footprint "R0805")
      (description "RES SMD 1K OHM 1% 1/8W 0805")
      (fields
        (field (name "MANUFACTURER") "Yageo")
        (field (name "MANUFACTURER PART NUMBER") "RC0805FR-071KL")
        (field (name ".CREATOR") "MM")
        (field (name ".CHECKED PCB") "RF")
        (field (name ".CHECKED SCH") "RF")
      )
      (libsource (lib "Integrated_Library_FEDEVEL_APR_2015") (part "RC0805FR-071KL"))
    )
    (comp (ref "R13")
      (value "22R")
      (footprint "R0805")
      (description "RES SMD 22 OHM 1% 1/8W 0805")
      (fields
        (field (name "MANUFACTURER") "Yageo")
        (field (name "MANUFACTURER PART NUMBER") "RC0805FR-0722RL")
        (field (name ".CREATOR") "MM")
        (field (name ".CHECKED PCB") "RF")
        (field (name ".CHECKED SCH") "RF")
      )
      (libsource (lib "Integrated_Library_FEDEVEL_APR_2015") (part "RC0805FR-0722RL"))
    )
    (comp (ref "R14")
      (value "10k")
      (footprint "R0805")
      (description "RES SMD 10K OHM 1% 1/8W 0805")
      (fields
        (field (name "MANUFACTURER") "Yageo")
        (field (name "MANUFACTURER PART NUMBER") "RC0805FR-0710KL")
        (field (name ".CREATOR") "MM")
        (field (name ".CHECKED PCB") "RF")
        (field (name ".CHECKED SCH") "RF")
      )
      (libsource (lib "Integrated_Library_FEDEVEL_APR_2015") (part "RC0805FR-0710KL"))
    )
    (comp (ref "R15")
      (value "560R")
      (footprint "R0805")
      (description "RES SMD 560 OHM 1% 1/8W 0805")
      (fields
        (field (name "MANUFACTURER") "Yageo")
        (field (name "MANUFACTURER PART NUMBER") "RC0805FR-07560RL")
        (field (name ".CREATOR") "MM")
        (field (name ".CHECKED PCB") "RF")
        (field (name ".CHECKED SCH") "RF")
      )
      (libsource (lib "Integrated_Library_FEDEVEL_APR_2015") (part "RC0805FR-07560RL"))
    )
    (comp (ref "R16")
      (value "1M")
      (footprint "R0805")
      (description "RES SMD 1M OHM 1% 1/8W 0805")
      (fields
        (field (name "MANUFACTURER") "Yageo")
        (field (name "MANUFACTURER PART NUMBER") "RC0805FR-071ML")
        (field (name ".CREATOR") "MM")
        (field (name ".CHECKED PCB") "RF")
        (field (name ".CHECKED SCH") "RF")
      )
      (libsource (lib "Integrated_Library_FEDEVEL_APR_2015") (part "RC0805FR-071ML"))
    )
    (comp (ref "R17")
      (value "560R")
      (footprint "R0805")
      (description "RES SMD 560 OHM 1% 1/8W 0805")
      (fields
        (field (name "MANUFACTURER") "Yageo")
        (field (name "MANUFACTURER PART NUMBER") "RC0805FR-07560RL")
        (field (name ".CREATOR") "MM")
        (field (name ".CHECKED PCB") "RF")
        (field (name ".CHECKED SCH") "RF")
      )
      (libsource (lib "Integrated_Library_FEDEVEL_APR_2015") (part "RC0805FR-07560RL"))
    )
    (comp (ref "R18")
      (value "10k")
      (footprint "R0805")
      (description "RES SMD 10K OHM 1% 1/8W 0805")
      (fields
        (field (name "MANUFACTURER") "Yageo")
        (field (name "MANUFACTURER PART NUMBER") "RC0805FR-0710KL")
        (field (name ".CREATOR") "MM")
        (field (name ".CHECKED PCB") "RF")
        (field (name ".CHECKED SCH") "RF")
      )
      (libsource (lib "Integrated_Library_FEDEVEL_APR_2015") (part "RC0805FR-0710KL"))
    )
    (comp (ref "R19")
      (value "10k")
      (footprint "R0805")
      (description "RES SMD 10K OHM 1% 1/8W 0805")
      (fields
        (field (name "MANUFACTURER") "Yageo")
        (field (name "MANUFACTURER PART NUMBER") "RC0805FR-0710KL")
        (field (name ".CREATOR") "MM")
        (field (name ".CHECKED PCB") "RF")
        (field (name ".CHECKED SCH") "RF")
      )
      (libsource (lib "Integrated_Library_FEDEVEL_APR_2015") (part "RC0805FR-0710KL"))
    )
    (comp (ref "R20")
      (value "10k")
      (footprint "R0805")
      (description "RES SMD 10K OHM 1% 1/8W 0805")
      (fields
        (field (name "MANUFACTURER") "Yageo")
        (field (name "MANUFACTURER PART NUMBER") "RC0805FR-0710KL")
        (field (name ".CREATOR") "MM")
        (field (name ".CHECKED PCB") "RF")
        (field (name ".CHECKED SCH") "RF")
      )
      (libsource (lib "Integrated_Library_FEDEVEL_APR_2015") (part "RC0805FR-0710KL"))
    )
    (comp (ref "R21")
      (value "10k")
      (footprint "R0805")
      (description "RES SMD 10K OHM 1% 1/8W 0805")
      (fields
        (field (name "MANUFACTURER") "Yageo")
        (field (name "MANUFACTURER PART NUMBER") "RC0805FR-0710KL")
        (field (name ".CREATOR") "MM")
        (field (name ".CHECKED PCB") "RF")
        (field (name ".CHECKED SCH") "RF")
      )
      (libsource (lib "Integrated_Library_FEDEVEL_APR_2015") (part "RC0805FR-0710KL"))
    )
    (comp (ref "R22")
      (value "560R")
      (footprint "R0805")
      (description "RES SMD 560 OHM 1% 1/8W 0805")
      (fields
        (field (name "MANUFACTURER") "Yageo")
        (field (name "MANUFACTURER PART NUMBER") "RC0805FR-07560RL")
        (field (name ".CREATOR") "MM")
        (field (name ".CHECKED PCB") "RF")
        (field (name ".CHECKED SCH") "RF")
      )
      (libsource (lib "Integrated_Library_FEDEVEL_APR_2015") (part "RC0805FR-07560RL"))
    )
    (comp (ref "R23")
      (value "22R")
      (footprint "R0805")
      (description "RES SMD 22 OHM 1% 1/8W 0805")
      (fields
        (field (name "MANUFACTURER") "Yageo")
        (field (name "MANUFACTURER PART NUMBER") "RC0805FR-0722RL")
        (field (name ".CREATOR") "MM")
        (field (name ".CHECKED PCB") "RF")
        (field (name ".CHECKED SCH") "RF")
      )
      (libsource (lib "Integrated_Library_FEDEVEL_APR_2015") (part "RC0805FR-0722RL"))
    )
    (comp (ref "R24")
      (value "22R")
      (footprint "R0805")
      (description "RES SMD 22 OHM 1% 1/8W 0805")
      (fields
        (field (name "MANUFACTURER") "Yageo")
        (field (name "MANUFACTURER PART NUMBER") "RC0805FR-0722RL")
        (field (name ".CREATOR") "MM")
        (field (name ".CHECKED PCB") "RF")
        (field (name ".CHECKED SCH") "RF")
      )
      (libsource (lib "Integrated_Library_FEDEVEL_APR_2015") (part "RC0805FR-0722RL"))
    )
    (comp (ref "R25")
      (value "22R")
      (footprint "R0805")
      (description "RES SMD 22 OHM 1% 1/8W 0805")
      (fields
        (field (name "MANUFACTURER") "Yageo")
        (field (name "MANUFACTURER PART NUMBER") "RC0805FR-0722RL")
        (field (name ".CREATOR") "MM")
        (field (name ".CHECKED PCB") "RF")
        (field (name ".CHECKED SCH") "RF")
      )
      (libsource (lib "Integrated_Library_FEDEVEL_APR_2015") (part "RC0805FR-0722RL"))
    )
    (comp (ref "R26")
      (value "0R")
      (footprint "R0805")
      (description "RES 0.0 OHM 1/8W 0805 SMD")
      (fields
        (field (name "MANUFACTURER") "Yageo")
        (field (name "MANUFACTURER PART NUMBER") "RC0805JR-070RL")
        (field (name ".CHECKED PCB") "RF")
        (field (name ".CHECKED SCH") "RF")
      )
      (libsource (lib "Integrated_Library_FEDEVEL_APR_2015") (part "RC0805JR-070RL"))
    )
    (comp (ref "R27")
      (value "0R")
      (footprint "R0805")
      (description "RES 0.0 OHM 1/8W 0805 SMD")
      (fields
        (field (name "MANUFACTURER") "Yageo")
        (field (name "MANUFACTURER PART NUMBER") "RC0805JR-070RL")
        (field (name ".CHECKED PCB") "RF")
        (field (name ".CHECKED SCH") "RF")
      )
      (libsource (lib "Integrated_Library_FEDEVEL_APR_2015") (part "RC0805JR-070RL"))
    )
    (comp (ref "R28")
      (value "0R")
      (footprint "R0805")
      (description "RES 0.0 OHM 1/8W 0805 SMD")
      (fields
        (field (name "MANUFACTURER") "Yageo")
        (field (name "MANUFACTURER PART NUMBER") "RC0805JR-070RL")
        (field (name ".CHECKED PCB") "RF")
        (field (name ".CHECKED SCH") "RF")
      )
      (libsource (lib "Integrated_Library_FEDEVEL_APR_2015") (part "RC0805JR-070RL"))
    )
    (comp (ref "SCKT FOR U1")
      (value "28-DIP Socket")
      (footprint "28_DIP_7.62mm_SOCKET")
      (description "CONN IC DIP SOCKET 28POS TIN")
      (fields
        (field (name "MANUFACTURER") "3M")
        (field (name "MANUFACTURER PART NUMBER") "4828-3004-CP")
        (field (name ".CREATOR") "MM")
        (field (name ".CHECKED PCB") "RF")
        (field (name ".CHECKED SCH") "RF")
      )
      (libsource (lib "Integrated_Library_FEDEVEL_APR_2015") (part "4828-3004-CP"))
    )
    (comp (ref "SW1")
      (value "1825910-6")
      (footprint "1825910-6")
      (description "SWITCH TACTILE SPST-NO 0.05A 24V")
      (fields
        (field (name "MANUFACTURER") "TE Connectivity")
        (field (name ".CREATOR") "MM")
        (field (name ".CHECKED PCB") "RF")
        (field (name ".CHECKED SCH") "RF")
      )
      (libsource (lib "Integrated_Library_FEDEVEL_APR_2015") (part "1825910-6"))
    )
    (comp (ref "SW2")
      (value "1825910-6")
      (footprint "1825910-6")
      (description "SWITCH TACTILE SPST-NO 0.05A 24V")
      (fields
        (field (name "MANUFACTURER") "TE Connectivity")
        (field (name ".CREATOR") "MM")
        (field (name ".CHECKED PCB") "RF")
        (field (name ".CHECKED SCH") "RF")
      )
      (libsource (lib "Integrated_Library_FEDEVEL_APR_2015") (part "1825910-6"))
    )
    (comp (ref "U1")
      (value "ATMEGA328P-PU")
      (footprint "28_DIP_7.62mm")
      (description "IC MCU 8BIT 32KB FLASH 28DIP")
      (fields
        (field (name "MANUFACTURER") "Atmel")
        (field (name ".CREATOR") "MM")
        (field (name ".CHECKED PCB") "RF")
        (field (name ".CHECKED SCH") "RF")
      )
      (libsource (lib "Integrated_Library_FEDEVEL_APR_2015") (part "ATMEGA328P-PU"))
    )
    (comp (ref "U2")
      (value "ATMEGA16U2-AU")
      (footprint "TQFP32")
      (description "IC MCU 8BIT 16KB FLASH 32TQFP")
      (fields
        (field (name "MANUFACTURER") "Atmel")
        (field (name ".CREATOR") "MM")
        (field (name ".CHECKED PCB") "RF")
        (field (name ".CHECKED SCH") "RF")
      )
      (libsource (lib "Integrated_Library_FEDEVEL_APR_2015") (part "ATMEGA16U2-AU"))
    )
    (comp (ref "U3")
      (value "TL1963A-33DCQR")
      (footprint "DCQ (R-PDSO-G6)")
      (description "IC REG LDO 3.3V 1.5A SOT223-6")
      (fields
        (field (name "MANUFACTURER") "Texas Instruments")
        (field (name ".CREATOR") "MM")
        (field (name ".CHECKED PCB") "RF")
        (field (name ".CHECKED SCH") "RF")
      )
      (libsource (lib "Integrated_Library_FEDEVEL_APR_2015") (part "TL1963A-33DCQR"))
    )
    (comp (ref "U4")
      (value "SN74AHC1G09DBVR")
      (footprint "DBV_SOT_23_5")
      (description "IC GATE AND SGL 2INP SOT23-5")
      (fields (field (name "MANUFACTURER") "Texas Instruments") (field (name ".CREATOR") "MM"))
      (libsource (lib "Integrated_Library_FEDEVEL_APR_2015") (part "SN74AHC1G09DBVR"))
    )
    (comp (ref "U5")
      (value "SN74AHC1G09DBVR")
      (footprint "DBV_SOT_23_5")
      (description "IC GATE AND SGL 2INP SOT23-5")
      (fields (field (name "MANUFACTURER") "Texas Instruments") (field (name ".CREATOR") "MM"))
      (libsource (lib "Integrated_Library_FEDEVEL_APR_2015") (part "SN74AHC1G09DBVR"))
    )
    (comp (ref "U6")
      (value "SN74AHC1G09DBVR")
      (footprint "DBV_SOT_23_5")
      (description "IC GATE AND SGL 2INP SOT23-5")
      (fields (field (name "MANUFACTURER") "Texas Instruments") (field (name ".CREATOR") "MM"))
      (libsource (lib "Integrated_Library_FEDEVEL_APR_2015") (part "SN74AHC1G09DBVR"))
    )
    (comp (ref "U7")
      (value "SN74AHC1G09DBVR")
      (footprint "DBV_SOT_23_5")
      (description "IC GATE AND SGL 2INP SOT23-5")
      (fields (field (name "MANUFACTURER") "Texas Instruments") (field (name ".CREATOR") "MM"))
      (libsource (lib "Integrated_Library_FEDEVEL_APR_2015") (part "SN74AHC1G09DBVR"))
    )
    (comp (ref "Y1")
      (value "ABM7-16.000MHZ-D2Y-T")
      (footprint "ABM7_v1_1_BIG")
      (description "CRYSTAL 16MHZ 18PF SMD")
      (fields
        (field (name "MANUFACTURER") "Abracon LLC")
        (field (name ".CREATOR") "MM")
        (field (name ".CHECKED PCB") "RF")
        (field (name ".CHECKED SCH") "RF")
      )
      (libsource (lib "Integrated_Library_FEDEVEL_APR_2015") (part "ABM7-16.000MHZ-D2Y-T"))
    )
    (comp (ref "Y2")
      (value "ABM7-16.000MHZ-D2Y-T")
      (footprint "ABM7_v1_1_BIG")
      (description "CRYSTAL 16MHZ 18PF SMD")
      (fields
        (field (name "MANUFACTURER") "Abracon LLC")
        (field (name ".CREATOR") "MM")
        (field (name ".CHECKED PCB") "RF")
        (field (name ".CHECKED SCH") "RF")
      )
      (libsource (lib "Integrated_Library_FEDEVEL_APR_2015") (part "ABM7-16.000MHZ-D2Y-T"))
    )
    (comp (ref "Z1")
      (value "CG0603MLC-05E")
      (footprint "R0603")
      (description "VARISTOR 0603")
      (fields
        (field (name "MANUFACTURER") "Bourns Inc.")
        (field (name ".CREATOR") "MM")
        (field (name ".CHECKED PCB") "RF")
        (field (name ".CHECKED SCH") "RF")
      )
      (libsource (lib "Integrated_Library_FEDEVEL_APR_2015") (part "CG0603MLC-05E"))
    )
    (comp (ref "Z2")
      (value "CG0603MLC-05E")
      (footprint "R0603")
      (description "VARISTOR 0603")
      (fields
        (field (name "MANUFACTURER") "Bourns Inc.")
        (field (name ".CREATOR") "MM")
        (field (name ".CHECKED PCB") "RF")
        (field (name ".CHECKED SCH") "RF")
      )
      (libsource (lib "Integrated_Library_FEDEVEL_APR_2015") (part "CG0603MLC-05E"))
    )
  )
  (nets
    (net (code "1") (name "+3V3") (class "Default")
      (node (ref "C13") (pin "1") (pinfunction "1_1") (pintype "passive"))
      (node (ref "C16") (pin "1") (pinfunction "1_1") (pintype "passive"))
      (node (ref "J1") (pin "4") (pinfunction "4_4") (pintype "passive"))
      (node (ref "JP4") (pin "3") (pinfunction "3_3") (pintype "passive"))
      (node (ref "R28") (pin "1") (pinfunction "1_1") (pintype "passive"))
      (node (ref "U3") (pin "4") (pinfunction "OUT_4") (pintype "passive"))
      (node (ref "U3") (pin "5") (pinfunction "SENSE_5") (pintype "passive"))
    )
    (net (code "2") (name "+5V") (class "Default")
      (node (ref "C12") (pin "1") (pinfunction "1_1") (pintype "passive"))
      (node (ref "C14") (pin "1") (pinfunction "1_1") (pintype "passive"))
      (node (ref "C2") (pin "1") (pinfunction "1_1") (pintype "passive"))
      (node (ref "C6") (pin "1") (pinfunction "1_1") (pintype "passive"))
      (node (ref "J1") (pin "5") (pinfunction "5_5") (pintype "passive"))
      (node (ref "J8") (pin "1") (pinfunction "1_1") (pintype "passive"))
      (node (ref "JP4") (pin "1") (pinfunction "1_1") (pintype "passive"))
      (node (ref "L1") (pin "2") (pinfunction "2_2") (pintype "passive"))
      (node (ref "R27") (pin "2") (pinfunction "2_2") (pintype "passive"))
      (node (ref "U2") (pin "31") (pinfunction "UVCC_31") (pintype "passive"))
      (node (ref "U3") (pin "1") (pinfunction "~{SHDN}_1") (pintype "passive"))
      (node (ref "U3") (pin "2") (pinfunction "IN_2") (pintype "passive"))
    )
    (net (code "3") (name "+5V{slash}3V3") (class "Default")
      (node (ref "C15") (pin "1") (pinfunction "1_1") (pintype "passive"))
      (node (ref "C17") (pin "1") (pinfunction "1_1") (pintype "passive"))
      (node (ref "C26") (pin "1") (pinfunction "1_1") (pintype "passive"))
      (node (ref "C28") (pin "1") (pinfunction "1_1") (pintype "passive"))
      (node (ref "C29") (pin "1") (pinfunction "1_1") (pintype "passive"))
      (node (ref "C30") (pin "1") (pinfunction "1_1") (pintype "passive"))
      (node (ref "C34") (pin "1") (pinfunction "1_1") (pintype "passive"))
      (node (ref "C8") (pin "1") (pinfunction "1_1") (pintype "passive"))
      (node (ref "D5") (pin "1") (pinfunction "Cathode_1") (pintype "passive"))
      (node (ref "D6") (pin "1") (pinfunction "Cathode_1") (pintype "passive"))
      (node (ref "FB1") (pin "1") (pinfunction "1_1") (pintype "passive"))
      (node (ref "FB2") (pin "1") (pinfunction "1_1") (pintype "passive"))
      (node (ref "FB3") (pin "1") (pinfunction "1_1") (pintype "passive"))
      (node (ref "J1") (pin "2") (pinfunction "2_2") (pintype "passive"))
      (node (ref "J5") (pin "2") (pinfunction "2_2") (pintype "passive"))
      (node (ref "J6") (pin "2") (pinfunction "2_2") (pintype "passive"))
      (node (ref "JP4") (pin "2") (pinfunction "2_2") (pintype "passive"))
      (node (ref "R1") (pin "2") (pinfunction "2_2") (pintype "passive"))
      (node (ref "R14") (pin "2") (pinfunction "2_2") (pintype "passive"))
      (node (ref "R15") (pin "2") (pinfunction "2_2") (pintype "passive"))
      (node (ref "R17") (pin "2") (pinfunction "2_2") (pintype "passive"))
      (node (ref "R18") (pin "2") (pinfunction "2_2") (pintype "passive"))
      (node (ref "R19") (pin "2") (pinfunction "2_2") (pintype "passive"))
      (node (ref "R2") (pin "2") (pinfunction "2_2") (pintype "passive"))
      (node (ref "R20") (pin "2") (pinfunction "2_2") (pintype "passive"))
      (node (ref "R21") (pin "2") (pinfunction "2_2") (pintype "passive"))
      (node (ref "R27") (pin "1") (pinfunction "1_1") (pintype "passive"))
      (node (ref "R28") (pin "2") (pinfunction "2_2") (pintype "passive"))
      (node (ref "R3") (pin "2") (pinfunction "2_2") (pintype "passive"))
      (node (ref "R4") (pin "2") (pinfunction "2_2") (pintype "passive"))
      (node (ref "U4") (pin "5") (pinfunction "VCC_5") (pintype "power_in"))
      (node (ref "U5") (pin "5") (pinfunction "VCC_5") (pintype "power_in"))
      (node (ref "U6") (pin "5") (pinfunction "VCC_5") (pintype "power_in"))
      (node (ref "U7") (pin "5") (pinfunction "VCC_5") (pintype "power_in"))
    )
    (net (code "4") (name "+AREF") (class "Default")
      (node (ref "C21") (pin "1") (pinfunction "1_1") (pintype "passive"))
      (node (ref "C24") (pin "1") (pinfunction "1_1") (pintype "passive"))
      (node (ref "J4") (pin "8") (pinfunction "8_8") (pintype "passive"))
      (node (ref "U1") (pin "21") (pinfunction "AREF_21") (pintype "passive"))
    )
    (net (code "5") (name "/+3V3_16U2_UCAP") (class "Default")
      (node (ref "C7") (pin "2") (pinfunction "2_2") (pintype "passive"))
      (node (ref "R26") (pin "1") (pinfunction "1_1") (pintype "passive"))
      (node (ref "U2") (pin "27") (pinfunction "UCAP_27") (pintype "passive"))
    )
    (net (code "6") (name "/+5V_USB") (class "Default")
      (node (ref "C1") (pin "1") (pinfunction "1_1") (pintype "passive"))
      (node (ref "J7") (pin "1") (pinfunction "P1_1") (pintype "passive"))
      (node (ref "L1") (pin "1") (pinfunction "1_1") (pintype "passive"))
    )
    (net (code "7") (name "/+5V{slash}3V3_16U2") (class "Default")
      (node (ref "C3") (pin "1") (pinfunction "1_1") (pintype "passive"))
      (node (ref "C4") (pin "1") (pinfunction "1_1") (pintype "passive"))
      (node (ref "C5") (pin "1") (pinfunction "1_1") (pintype "passive"))
      (node (ref "FB1") (pin "2") (pinfunction "2_2") (pintype "passive"))
      (node (ref "R26") (pin "2") (pinfunction "2_2") (pintype "passive"))
      (node (ref "U2") (pin "32") (pinfunction "AVCC_32") (pintype "passive"))
      (node (ref "U2") (pin "4") (pinfunction "VCC_4") (pintype "passive"))
    )
    (net (code "8") (name "/+5V{slash}3V3_328P_AVCC") (class "Default")
      (node (ref "C22") (pin "1") (pinfunction "1_1") (pintype "passive"))
      (node (ref "C23") (pin "1") (pinfunction "1_1") (pintype "passive"))
      (node (ref "FB3") (pin "2") (pinfunction "2_2") (pintype "passive"))
      (node (ref "U1") (pin "20") (pinfunction "AVCC_20") (pintype "passive"))
    )
    (net (code "9") (name "/+5V{slash}3V3_328P_VCC") (class "Default")
      (node (ref "C19") (pin "1") (pinfunction "1_1") (pintype "passive"))
      (node (ref "C20") (pin "1") (pinfunction "1_1") (pintype "passive"))
      (node (ref "FB2") (pin "2") (pinfunction "2_2") (pintype "passive"))
      (node (ref "U1") (pin "7") (pinfunction "VCC_7") (pintype "passive"))
    )
    (net (code "10") (name "/16U2PROG_328P_RESETn") (class "Default")
      (node (ref "JP1") (pin "2") (pinfunction "2_2") (pintype "passive"))
      (node (ref "R1") (pin "1") (pinfunction "1_1") (pintype "passive"))
      (node (ref "U2") (pin "13") (pinfunction "~{CTS}_/~{_HWB}_/_T0_/_AIN6_/_INT7_/_PD7_13") (pintype "passive"))
    )
    (net (code "11") (name "/16U2_16MHZ_XTAL1") (class "Default")
      (node (ref "C10") (pin "2") (pinfunction "2_2") (pintype "passive"))
      (node (ref "R9") (pin "1") (pinfunction "1_1") (pintype "passive"))
      (node (ref "U2") (pin "1") (pinfunction "XTAL1_1") (pintype "passive"))
      (node (ref "Y2") (pin "1") (pinfunction "1_1") (pintype "passive"))
    )
    (net (code "12") (name "/16U2_16MHZ_XTAL2") (class "Default")
      (node (ref "C9") (pin "2") (pinfunction "2_2") (pintype "passive"))
      (node (ref "R9") (pin "2") (pinfunction "2_2") (pintype "passive"))
      (node (ref "U2") (pin "2") (pinfunction "XTAL2_/_PC0_2") (pintype "passive"))
      (node (ref "Y2") (pin "2") (pinfunction "2_2") (pintype "passive"))
    )
    (net (code "13") (name "/16U2_BUF_RESETn") (class "Default")
      (node (ref "C31") (pin "1") (pinfunction "1_1") (pintype "passive"))
      (node (ref "R23") (pin "2") (pinfunction "2_2") (pintype "passive"))
      (node (ref "U5") (pin "1") (pinfunction "A_1") (pintype "passive"))
      (node (ref "U5") (pin "2") (pinfunction "B_2") (pintype "passive"))
    )
    (net (code "14") (name "/16U2_HDR_RESETn") (class "Default")
      (node (ref "J6") (pin "5") (pinfunction "5_5") (pintype "passive"))
      (node (ref "JP3") (pin "3") (pinfunction "3_3") (pintype "passive"))
    )
    (net (code "15") (name "/16U2_MISO") (class "Default")
      (node (ref "J6") (pin "1") (pinfunction "1_1") (pintype "passive"))
      (node (ref "U2") (pin "17") (pinfunction "PDO_/_MISO_/_PCINT3_/_PB3_17") (pintype "passive"))
    )
    (net (code "16") (name "/16U2_MOSI") (class "Default")
      (node (ref "J6") (pin "4") (pinfunction "4_4") (pintype "passive"))
      (node (ref "U2") (pin "16") (pinfunction "PDI_/_MOSI_/_PCINT2_/_PB2_16") (pintype "passive"))
    )
    (net (code "17") (name "/16U2_PB4") (class "Default")
      (node (ref "JP2") (pin "1") (pinfunction "1_1") (pintype "passive"))
      (node (ref "JP3") (pin "2") (pinfunction "2_2") (pintype "passive"))
      (node (ref "U2") (pin "18") (pinfunction "T1_/_PCINT4_/_PB4_18") (pintype "passive"))
    )
    (net (code "18") (name "/16U2_PB5") (class "Default")
      (node (ref "JP2") (pin "3") (pinfunction "3_3") (pintype "passive"))
      (node (ref "U2") (pin "19") (pinfunction "PCINT5_/_PB5_19") (pintype "passive"))
    )
    (net (code "19") (name "/16U2_PB6") (class "Default")
      (node (ref "JP2") (pin "2") (pinfunction "2_2") (pintype "passive"))
      (node (ref "U2") (pin "20") (pinfunction "PCINT6_/_PB6_20") (pintype "passive"))
    )
    (net (code "20") (name "/16U2_PB7") (class "Default")
      (node (ref "JP2") (pin "4") (pinfunction "4_4") (pintype "passive"))
      (node (ref "U2") (pin "21") (pinfunction "OC.0A_/_OC.1C_/_PCINT7_/_PB7_21") (pintype "passive"))
    )
    (net (code "21") (name "/16U2_RESETn") (class "Default")
      (node (ref "JP3") (pin "4") (pinfunction "4_4") (pintype "passive"))
      (node (ref "R4") (pin "1") (pinfunction "1_1") (pintype "passive"))
      (node (ref "U2") (pin "24") (pinfunction "PC1_/~{_RESET}_/_DW_24") (pintype "passive"))
      (node (ref "U5") (pin "4") (pinfunction "Y_4") (pintype "passive"))
    )
    (net (code "22") (name "/16U2_RXD") (class "Default")
      (node (ref "R11") (pin "1") (pinfunction "1_1") (pintype "passive"))
      (node (ref "U2") (pin "8") (pinfunction "RXD1_/_AIN1_/_INT2_/_PD2_8") (pintype "passive"))
    )
    (net (code "23") (name "/16U2_RX_LED") (class "Default")
      (node (ref "D4") (pin "1") (pinfunction "cathode_1") (pintype "passive"))
      (node (ref "U2") (pin "10") (pinfunction "AIN3_/_INT5_/_PD4_10") (pintype "passive"))
    )
    (net (code "24") (name "/16U2_SCLK") (class "Default")
      (node (ref "J6") (pin "3") (pinfunction "3_3") (pintype "passive"))
      (node (ref "R5") (pin "2") (pinfunction "2_2") (pintype "passive"))
    )
    (net (code "25") (name "/16U2_SCLK_R") (class "Default")
      (node (ref "R5") (pin "1") (pinfunction "1_1") (pintype "passive"))
      (node (ref "U2") (pin "15") (pinfunction "SCLK_/_PCINT1_/_PB1_15") (pintype "passive"))
    )
    (net (code "26") (name "/16U2_TXD") (class "Default")
      (node (ref "R10") (pin "1") (pinfunction "1_1") (pintype "passive"))
      (node (ref "U2") (pin "9") (pinfunction "TXD1_/_INT3_/_PD3_9") (pintype "passive"))
    )
    (net (code "27") (name "/16U2_TX_LED") (class "Default")
      (node (ref "D3") (pin "1") (pinfunction "cathode_1") (pintype "passive"))
      (node (ref "U2") (pin "11") (pinfunction "XCK_/_AIN4_/_PCINT12_/_PD5_11") (pintype "passive"))
    )
    (net (code "28") (name "/328P_16MHZ_XTAL1") (class "Default")
      (node (ref "C27") (pin "2") (pinfunction "2_2") (pintype "passive"))
      (node (ref "R16") (pin "1") (pinfunction "1_1") (pintype "passive"))
      (node (ref "U1") (pin "9") (pinfunction "PB6_/_PCINT6_/_TOSC1_/_XTAL1_9") (pintype "passive"))
      (node (ref "Y1") (pin "1") (pinfunction "1_1") (pintype "passive"))
    )
    (net (code "29") (name "/328P_16MHZ_XTAL2") (class "Default")
      (node (ref "C25") (pin "2") (pinfunction "2_2") (pintype "passive"))
      (node (ref "R16") (pin "2") (pinfunction "2_2") (pintype "passive"))
      (node (ref "U1") (pin "10") (pinfunction "PB7_/_PCINT7_/_TOSC2_/_XTAL2_10") (pintype "passive"))
      (node (ref "Y1") (pin "2") (pinfunction "2_2") (pintype "passive"))
    )
    (net (code "30") (name "/328P_AUTORESETn") (class "Default")
      (node (ref "C11") (pin "1") (pinfunction "1_1") (pintype "passive"))
      (node (ref "R18") (pin "1") (pinfunction "1_1") (pintype "passive"))
      (node (ref "U6") (pin "1") (pinfunction "A_1") (pintype "passive"))
    )
    (net (code "31") (name "/328P_BUF_RESETn") (class "Default")
      (node (ref "C32") (pin "1") (pinfunction "1_1") (pintype "passive"))
      (node (ref "R24") (pin "2") (pinfunction "2_2") (pintype "passive"))
      (node (ref "U6") (pin "2") (pinfunction "B_2") (pintype "passive"))
    )
    (net (code "32") (name "/328P_RESETn") (class "Default")
      (node (ref "J1") (pin "3") (pinfunction "3_3") (pintype "passive"))
      (node (ref "J5") (pin "5") (pinfunction "5_5") (pintype "passive"))
      (node (ref "JP3") (pin "1") (pinfunction "1_1") (pintype "passive"))
      (node (ref "R14") (pin "1") (pinfunction "1_1") (pintype "passive"))
      (node (ref "U1") (pin "1") (pinfunction "PC6_/_PCINT14_/~{_RESET}_1") (pintype "passive"))
      (node (ref "U6") (pin "4") (pinfunction "Y_4") (pintype "passive"))
    )
    (net (code "33") (name "/AD0") (class "Default")
      (node (ref "J2") (pin "1") (pinfunction "1_1") (pintype "passive"))
      (node (ref "U1") (pin "23") (pinfunction "PCINT8_/_ADC0_/_PC0_23") (pintype "passive"))
    )
    (net (code "34") (name "/AD1") (class "Default")
      (node (ref "J2") (pin "2") (pinfunction "2_2") (pintype "passive"))
      (node (ref "U1") (pin "24") (pinfunction "PCINT9_/_ADC1_/_PC1_24") (pintype "passive"))
    )
    (net (code "35") (name "/AD2") (class "Default")
      (node (ref "J2") (pin "3") (pinfunction "3_3") (pintype "passive"))
      (node (ref "U1") (pin "25") (pinfunction "PCINT10_/_ADC2_/_PC2_25") (pintype "passive"))
    )
    (net (code "36") (name "/AD3") (class "Default")
      (node (ref "J2") (pin "4") (pinfunction "4_4") (pintype "passive"))
      (node (ref "U1") (pin "26") (pinfunction "PCINT11_/_ADC3_/_PC3_26") (pintype "passive"))
    )
    (net (code "37") (name "/AD4{slash}SDA") (class "Default")
      (node (ref "J2") (pin "5") (pinfunction "5_5") (pintype "passive"))
      (node (ref "J4") (pin "9") (pinfunction "9_9") (pintype "passive"))
      (node (ref "U1") (pin "27") (pinfunction "SDA_/_PCINT12_/_ADC4_/_PC4_27") (pintype "passive"))
    )
    (net (code "38") (name "/AD5{slash}SCL") (class "Default")
      (node (ref "J2") (pin "6") (pinfunction "6_6") (pintype "passive"))
      (node (ref "J4") (pin "10") (pinfunction "10_10") (pintype "passive"))
      (node (ref "U1") (pin "28") (pinfunction "SCL_/_PCINT13_/_ADC5_/_PC5_28") (pintype "passive"))
    )
    (net (code "39") (name "/BUTTON_RESETn") (class "Default")
      (node (ref "D6") (pin "2") (pinfunction "Anode_2") (pintype "passive"))
      (node (ref "R20") (pin "1") (pinfunction "1_1") (pintype "passive"))
      (node (ref "R24") (pin "1") (pinfunction "1_1") (pintype "passive"))
      (node (ref "SW1") (pin "1") (pinfunction "1_1") (pintype "passive"))
      (node (ref "SW1") (pin "2") (pinfunction "2_2") (pintype "passive"))
    )
    (net (code "40") (name "/CON_USB_N") (class "Default")
      (node (ref "J7") (pin "2") (pinfunction "P2_2") (pintype "passive"))
      (node (ref "R6") (pin "1") (pinfunction "1_1") (pintype "passive"))
      (node (ref "Z1") (pin "2") (pinfunction "2_2") (pintype "passive"))
    )
    (net (code "41") (name "/CON_USB_P") (class "Default")
      (node (ref "J7") (pin "3") (pinfunction "P3_3") (pintype "passive"))
      (node (ref "R7") (pin "1") (pinfunction "1_1") (pintype "passive"))
      (node (ref "Z2") (pin "2") (pinfunction "2_2") (pintype "passive"))
    )
    (net (code "42") (name "/IO0") (class "Default")
      (node (ref "J3") (pin "1") (pinfunction "1_1") (pintype "passive"))
      (node (ref "R10") (pin "2") (pinfunction "2_2") (pintype "passive"))
      (node (ref "U1") (pin "2") (pinfunction "RXD_/_PCINT16_/_PD0_2") (pintype "passive"))
    )
    (net (code "43") (name "/IO1") (class "Default")
      (node (ref "J3") (pin "2") (pinfunction "2_2") (pintype "passive"))
      (node (ref "R11") (pin "2") (pinfunction "2_2") (pintype "passive"))
      (node (ref "U1") (pin "3") (pinfunction "TXD_/_PCINT17_/_PD1_3") (pintype "passive"))
    )
    (net (code "44") (name "/IO2") (class "Default")
      (node (ref "J3") (pin "3") (pinfunction "3_3") (pintype "passive"))
      (node (ref "U1") (pin "4") (pinfunction "INT0_/_PCINT18_/_PD2_4") (pintype "passive"))
    )
    (net (code "45") (name "/IO3") (class "Default")
      (node (ref "J3") (pin "4") (pinfunction "4_4") (pintype "passive"))
      (node (ref "U1") (pin "5") (pinfunction "OC2B_/_INT1_/_PCINT19_/_PD3_5") (pintype "passive"))
    )
    (net (code "46") (name "/IO4") (class "Default")
      (node (ref "J3") (pin "5") (pinfunction "5_5") (pintype "passive"))
      (node (ref "U1") (pin "6") (pinfunction "XCK_/_T0_/_PCINT20_/_PD4_6") (pintype "passive"))
    )
    (net (code "47") (name "/IO5") (class "Default")
      (node (ref "J3") (pin "6") (pinfunction "6_6") (pintype "passive"))
      (node (ref "U1") (pin "11") (pinfunction "OC0B_/_T1_/_PCINT21_/_PD5_11") (pintype "passive"))
    )
    (net (code "48") (name "/IO6") (class "Default")
      (node (ref "J3") (pin "7") (pinfunction "7_7") (pintype "passive"))
      (node (ref "U1") (pin "12") (pinfunction "OC0A_/_AIN0_/_PCINT22_/_PD6_12") (pintype "passive"))
    )
    (net (code "49") (name "/IO7") (class "Default")
      (node (ref "J3") (pin "8") (pinfunction "8_8") (pintype "passive"))
      (node (ref "U1") (pin "13") (pinfunction "AIN1_/_PCINT23_/_PD7_13") (pintype "passive"))
    )
    (net (code "50") (name "/IO8") (class "Default")
      (node (ref "J4") (pin "1") (pinfunction "1_1") (pintype "passive"))
      (node (ref "R22") (pin "1") (pinfunction "1_1") (pintype "passive"))
      (node (ref "U1") (pin "14") (pinfunction "CLKO_/_ICP1_/_PCINT0_/_PB0_14") (pintype "passive"))
    )
    (net (code "51") (name "/IO9") (class "Default")
      (node (ref "J4") (pin "2") (pinfunction "2_2") (pintype "passive"))
      (node (ref "U1") (pin "15") (pinfunction "OC1A_/_PCINT1_/_PB1_15") (pintype "passive"))
    )
    (net (code "52") (name "/MISO") (class "Default")
      (node (ref "J4") (pin "5") (pinfunction "5_5") (pintype "passive"))
      (node (ref "J5") (pin "1") (pinfunction "1_1") (pintype "passive"))
      (node (ref "U1") (pin "18") (pinfunction "MISO_/_PCINT4_/_PB4_18") (pintype "passive"))
    )
    (net (code "53") (name "/MOSI") (class "Default")
      (node (ref "J4") (pin "4") (pinfunction "4_4") (pintype "passive"))
      (node (ref "J5") (pin "4") (pinfunction "4_4") (pintype "passive"))
      (node (ref "U1") (pin "17") (pinfunction "MOSI_/_OC2A_/_PCINT3_/_PB3_17") (pintype "passive"))
    )
    (net (code "54") (name "/SCK") (class "Default")
      (node (ref "J4") (pin "6") (pinfunction "6_6") (pintype "passive"))
      (node (ref "J5") (pin "3") (pinfunction "3_3") (pintype "passive"))
      (node (ref "R13") (pin "2") (pinfunction "2_2") (pintype "passive"))
      (node (ref "U4") (pin "1") (pinfunction "A_1") (pintype "passive"))
      (node (ref "U4") (pin "2") (pinfunction "B_2") (pintype "passive"))
    )
    (net (code "55") (name "/SCK_R") (class "Default")
      (node (ref "R13") (pin "1") (pinfunction "1_1") (pintype "passive"))
      (node (ref "U1") (pin "19") (pinfunction "SCK_/_PCINT5_/_PB5_19") (pintype "passive"))
    )
    (net (code "56") (name "/SS") (class "Default")
      (node (ref "J4") (pin "3") (pinfunction "3_3") (pintype "passive"))
      (node (ref "U1") (pin "16") (pinfunction "~{SS}_/_OC1B_/_PCINT2_/_PB2_16") (pintype "passive"))
    )
    (net (code "57") (name "/USB_N") (class "Default")
      (node (ref "R6") (pin "2") (pinfunction "2_2") (pintype "passive"))
      (node (ref "U2") (pin "30") (pinfunction "D-_30") (pintype "passive"))
    )
    (net (code "58") (name "/USB_P") (class "Default")
      (node (ref "R7") (pin "2") (pinfunction "2_2") (pintype "passive"))
      (node (ref "U2") (pin "29") (pinfunction "D+_29") (pintype "passive"))
    )
    (net (code "59") (name "/USER_BUTTON") (class "Default")
      (node (ref "R21") (pin "1") (pinfunction "1_1") (pintype "passive"))
      (node (ref "R25") (pin "1") (pinfunction "1_1") (pintype "passive"))
      (node (ref "SW2") (pin "1") (pinfunction "1_1") (pintype "passive"))
      (node (ref "SW2") (pin "2") (pinfunction "2_2") (pintype "passive"))
    )
    (net (code "60") (name "/USER_BUTTON_BUF") (class "Default")
      (node (ref "C33") (pin "1") (pinfunction "1_1") (pintype "passive"))
      (node (ref "R25") (pin "2") (pinfunction "2_2") (pintype "passive"))
      (node (ref "U7") (pin "1") (pinfunction "A_1") (pintype "passive"))
      (node (ref "U7") (pin "2") (pinfunction "B_2") (pintype "passive"))
    )
    (net (code "61") (name "GND") (class "Default")
      (node (ref "C1") (pin "2") (pinfunction "2_2") (pintype "passive"))
      (node (ref "C10") (pin "1") (pinfunction "1_1") (pintype "passive"))
      (node (ref "C12") (pin "2") (pinfunction "2_2") (pintype "passive"))
      (node (ref "C13") (pin "2") (pinfunction "2_2") (pintype "passive"))
      (node (ref "C14") (pin "2") (pinfunction "2_2") (pintype "passive"))
      (node (ref "C15") (pin "2") (pinfunction "2_2") (pintype "passive"))
      (node (ref "C16") (pin "2") (pinfunction "2_2") (pintype "passive"))
      (node (ref "C17") (pin "2") (pinfunction "2_2") (pintype "passive"))
      (node (ref "C19") (pin "2") (pinfunction "2_2") (pintype "passive"))
      (node (ref "C2") (pin "2") (pinfunction "2_2") (pintype "passive"))
      (node (ref "C20") (pin "2") (pinfunction "2_2") (pintype "passive"))
      (node (ref "C21") (pin "2") (pinfunction "2_2") (pintype "passive"))
      (node (ref "C22") (pin "2") (pinfunction "2_2") (pintype "passive"))
      (node (ref "C23") (pin "2") (pinfunction "2_2") (pintype "passive"))
      (node (ref "C24") (pin "2") (pinfunction "2_2") (pintype "passive"))
      (node (ref "C25") (pin "1") (pinfunction "1_1") (pintype "passive"))
      (node (ref "C26") (pin "2") (pinfunction "2_2") (pintype "passive"))
      (node (ref "C27") (pin "1") (pinfunction "1_1") (pintype "passive"))
      (node (ref "C28") (pin "2") (pinfunction "2_2") (pintype "passive"))
      (node (ref "C29") (pin "2") (pinfunction "2_2") (pintype "passive"))
      (node (ref "C3") (pin "2") (pinfunction "2_2") (pintype "passive"))
      (node (ref "C30") (pin "2") (pinfunction "2_2") (pintype "passive"))
      (node (ref "C31") (pin "2") (pinfunction "2_2") (pintype "passive"))
      (node (ref "C32") (pin "2") (pinfunction "2_2") (pintype "passive"))
      (node (ref "C33") (pin "2") (pinfunction "2_2") (pintype "passive"))
      (node (ref "C34") (pin "2") (pinfunction "2_2") (pintype "passive"))
      (node (ref "C4") (pin "2") (pinfunction "2_2") (pintype "passive"))
      (node (ref "C5") (pin "2") (pinfunction "2_2") (pintype "passive"))
      (node (ref "C6") (pin "2") (pinfunction "2_2") (pintype "passive"))
      (node (ref "C7") (pin "1") (pinfunction "1_1") (pintype "passive"))
      (node (ref "C8") (pin "2") (pinfunction "2_2") (pintype "passive"))
      (node (ref "C9") (pin "1") (pinfunction "1_1") (pintype "passive"))
      (node (ref "D1") (pin "1") (pinfunction "cathode_1") (pintype "passive"))
      (node (ref "J1") (pin "6") (pinfunction "6_6") (pintype "passive"))
      (node (ref "J1") (pin "7") (pinfunction "7_7") (pintype "passive"))
      (node (ref "J4") (pin "7") (pinfunction "7_7") (pintype "passive"))
      (node (ref "J5") (pin "6") (pinfunction "6_6") (pintype "passive"))
      (node (ref "J6") (pin "6") (pinfunction "6_6") (pintype "passive"))
      (node (ref "J7") (pin "10") (pinfunction "10_10") (pintype "passive"))
      (node (ref "J7") (pin "11") (pinfunction "11_11") (pintype "passive"))
      (node (ref "J7") (pin "5") (pinfunction "P5_5") (pintype "passive"))
      (node (ref "J7") (pin "6") (pinfunction "6_6") (pintype "passive"))
      (node (ref "J7") (pin "7") (pinfunction "7_7") (pintype "passive"))
      (node (ref "J7") (pin "8") (pinfunction "8_8") (pintype "passive"))
      (node (ref "J7") (pin "9") (pinfunction "9_9") (pintype "passive"))
      (node (ref "J9") (pin "1") (pinfunction "1_1") (pintype "passive"))
      (node (ref "MH1") (pin "1") (pinfunction "1_1") (pintype "passive"))
      (node (ref "MH2") (pin "1") (pinfunction "1_1") (pintype "passive"))
      (node (ref "MH3") (pin "1") (pinfunction "1_1") (pintype "passive"))
      (node (ref "R12") (pin "2") (pinfunction "2_2") (pintype "passive"))
      (node (ref "R8") (pin "2") (pinfunction "2_2") (pintype "passive"))
      (node (ref "SW1") (pin "3") (pinfunction "MECH1_3") (pintype "passive"))
      (node (ref "SW1") (pin "4") (pinfunction "MECH2_4") (pintype "passive"))
      (node (ref "SW2") (pin "3") (pinfunction "MECH1_3") (pintype "passive"))
      (node (ref "SW2") (pin "4") (pinfunction "MECH2_4") (pintype "passive"))
      (node (ref "U1") (pin "22") (pinfunction "GND_2_22") (pintype "passive"))
      (node (ref "U1") (pin "8") (pinfunction "GND_1_8") (pintype "passive"))
      (node (ref "U2") (pin "28") (pinfunction "UGND_28") (pintype "passive"))
      (node (ref "U2") (pin "3") (pinfunction "GND_3") (pintype "passive"))
      (node (ref "U3") (pin "3") (pinfunction "GND_3") (pintype "passive"))
      (node (ref "U3") (pin "6") (pinfunction "EPAD_6") (pintype "passive"))
      (node (ref "U4") (pin "3") (pinfunction "GND_3") (pintype "power_in"))
      (node (ref "U5") (pin "3") (pinfunction "GND_3") (pintype "power_in"))
      (node (ref "U6") (pin "3") (pinfunction "GND_3") (pintype "power_in"))
      (node (ref "U7") (pin "3") (pinfunction "GND_3") (pintype "power_in"))
      (node (ref "Z1") (pin "1") (pinfunction "1_1") (pintype "passive"))
      (node (ref "Z2") (pin "1") (pinfunction "1_1") (pintype "passive"))
    )
    (net (code "62") (name "Net-(C11-Pad2)") (class "Default")
      (node (ref "C11") (pin "2") (pinfunction "2_2") (pintype "passive"))
      (node (ref "JP1") (pin "1") (pinfunction "1_1") (pintype "passive"))
    )
    (net (code "63") (name "Net-(D1-ANODE)") (class "Default")
      (node (ref "D1") (pin "2") (pinfunction "ANODE_2") (pintype "passive"))
      (node (ref "R17") (pin "1") (pinfunction "1_1") (pintype "passive"))
    )
    (net (code "64") (name "Net-(D2-ANODE)") (class "Default")
      (node (ref "D2") (pin "2") (pinfunction "ANODE_2") (pintype "passive"))
      (node (ref "R15") (pin "1") (pinfunction "1_1") (pintype "passive"))
    )
    (net (code "65") (name "Net-(D2-cathode)") (class "Default")
      (node (ref "D2") (pin "1") (pinfunction "cathode_1") (pintype "passive"))
      (node (ref "U4") (pin "4") (pinfunction "Y_4") (pintype "passive"))
    )
    (net (code "66") (name "Net-(D3-ANODE)") (class "Default")
      (node (ref "D3") (pin "2") (pinfunction "ANODE_2") (pintype "passive"))
      (node (ref "R2") (pin "1") (pinfunction "1_1") (pintype "passive"))
    )
    (net (code "67") (name "Net-(D4-ANODE)") (class "Default")
      (node (ref "D4") (pin "2") (pinfunction "ANODE_2") (pintype "passive"))
      (node (ref "R3") (pin "1") (pinfunction "1_1") (pintype "passive"))
    )
    (net (code "68") (name "Net-(D5-Anode)") (class "Default")
      (node (ref "D5") (pin "2") (pinfunction "Anode_2") (pintype "passive"))
      (node (ref "R19") (pin "1") (pinfunction "1_1") (pintype "passive"))
      (node (ref "R23") (pin "1") (pinfunction "1_1") (pintype "passive"))
    )
    (net (code "69") (name "Net-(J7-P4)") (class "Default")
      (node (ref "J7") (pin "4") (pinfunction "P4_4") (pintype "passive"))
      (node (ref "R8") (pin "1") (pinfunction "1_1") (pintype "passive"))
    )
    (net (code "70") (name "Net-(JP1-Pad3)") (class "Default")
      (node (ref "JP1") (pin "3") (pinfunction "3_3") (pintype "passive"))
      (node (ref "R12") (pin "1") (pinfunction "1_1") (pintype "passive"))
    )
    (net (code "71") (name "Net-(U7-Y)") (class "Default")
      (node (ref "R22") (pin "2") (pinfunction "2_2") (pintype "passive"))
      (node (ref "U7") (pin "4") (pinfunction "Y_4") (pintype "passive"))
    )
    (net (code "72") (name "unconnected-(J1-Pad1)") (class "Default")
      (node (ref "J1") (pin "1") (pinfunction "1_1") (pintype "passive+no_connect"))
    )
    (net (code "73") (name "unconnected-(J1-Pad8)") (class "Default")
      (node (ref "J1") (pin "8") (pinfunction "8_8") (pintype "passive+no_connect"))
    )
    (net (code "74") (name "unconnected-(MH4-Pad1)") (class "Default")
      (node (ref "MH4") (pin "1") (pinfunction "1_1") (pintype "passive+no_connect"))
    )
    (net (code "75") (name "unconnected-(U2-AIN0_{slash}_INT1_{slash}_PD1-Pad7)") (class "Default")
      (node (ref "U2") (pin "7") (pinfunction "AIN0_/_INT1_/_PD1_7") (pintype "passive+no_connect"))
    )
    (net (code "76") (name "unconnected-(U2-AIN2_{slash}_PCINT11_{slash}_PC2-Pad5)") (class "Default")
      (node (ref "U2") (pin "5") (pinfunction "AIN2_/_PCINT11_/_PC2_5") (pintype "passive+no_connect"))
    )
    (net (code "77") (name "unconnected-(U2-CLKO_{slash}_ICP1_{slash}_INT4_{slash}_PC7-Pad22)") (class "Default")
      (node (ref "U2") (pin "22") (pinfunction "CLKO_/_ICP1_/_INT4_/_PC7_22") (pintype "passive+no_connect"))
    )
    (net (code "78") (name "unconnected-(U2-OC.0B_{slash}_INT0_{slash}_PD0-Pad6)") (class "Default")
      (node (ref "U2") (pin "6") (pinfunction "OC.0B_/_INT0_/_PD0_6") (pintype "passive+no_connect"))
    )
    (net (code "79") (name "unconnected-(U2-OC.1A_{slash}_PCINT8_{slash}_PC6-Pad23)") (class "Default")
      (node (ref "U2") (pin "23") (pinfunction "OC.1A_/_PCINT8_/_PC6_23") (pintype "passive+no_connect"))
    )
    (net (code "80") (name "unconnected-(U2-OC.1B_{slash}_PCINT9_{slash}_PC5-Pad25)") (class "Default")
      (node (ref "U2") (pin "25") (pinfunction "OC.1B_/_PCINT9_/_PC5_25") (pintype "passive+no_connect"))
    )
    (net (code "81") (name "unconnected-(U2-PCINT10_{slash}_PC4-Pad26)") (class "Default")
      (node (ref "U2") (pin "26") (pinfunction "PCINT10_/_PC4_26") (pintype "passive+no_connect"))
    )
    (net (code "82") (name "unconnected-(U2-~{RTS}_{slash}_AIN5_{slash}_INT6_{slash}_PD6-Pad12)") (class "Default")
      (node (ref "U2") (pin "12") (pinfunction "~{RTS}_/_AIN5_/_INT6_/_PD6_12") (pintype "passive"))
    )
    (net (code "83") (name "unconnected-(U2-~{SS}_{slash}_PCINT0_{slash}_PB0-Pad14)") (class "Default")
      (node (ref "U2") (pin "14") (pinfunction "~{SS}_/_PCINT0_/_PB0_14") (pintype "passive+no_connect"))
    )
  )
)
